# 4ESC_v3_1_1.net
KiCad netlist of a schematic drawn in EAGLE
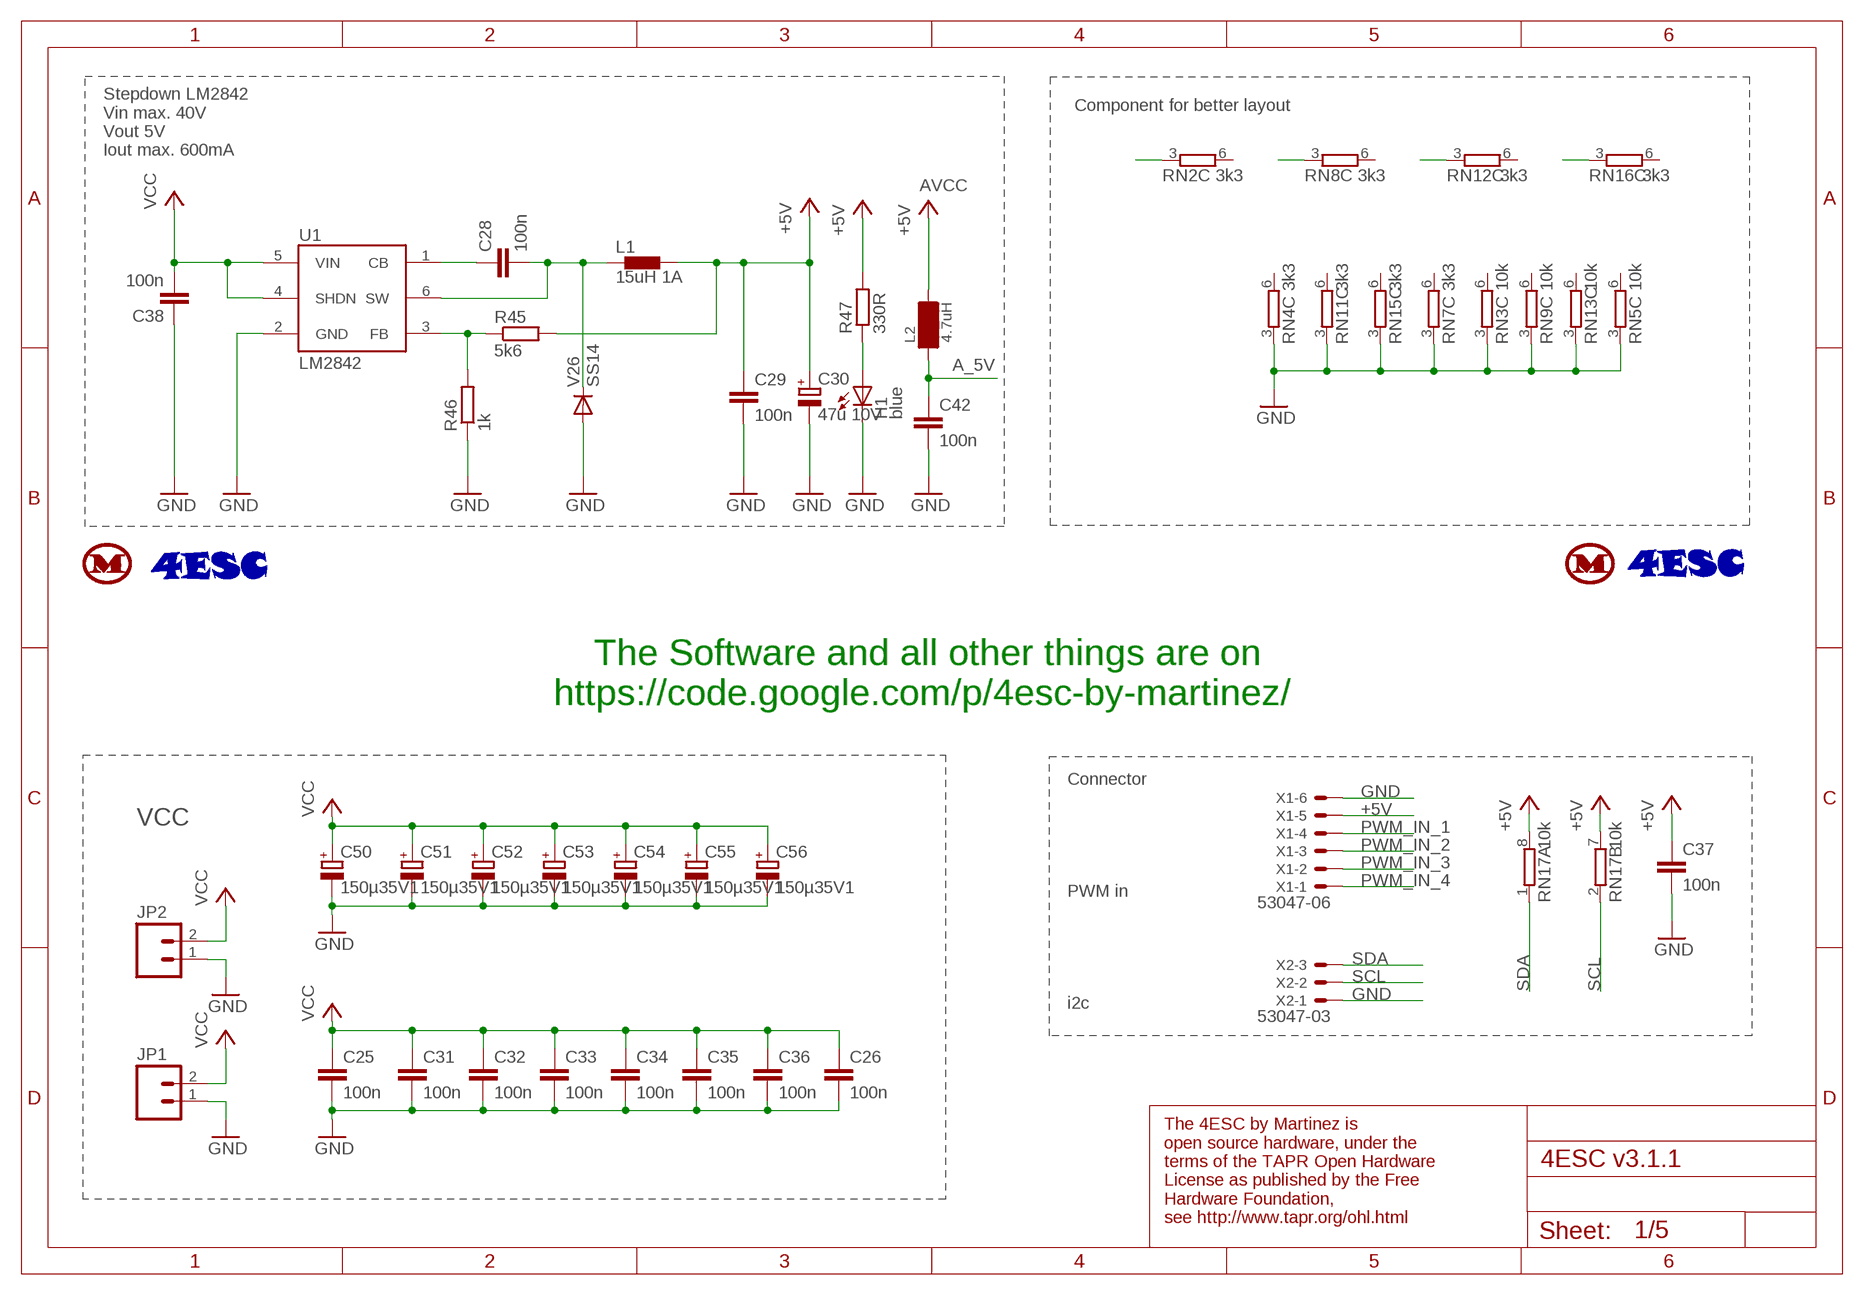
[diagram p0: schematic, sheet 1]
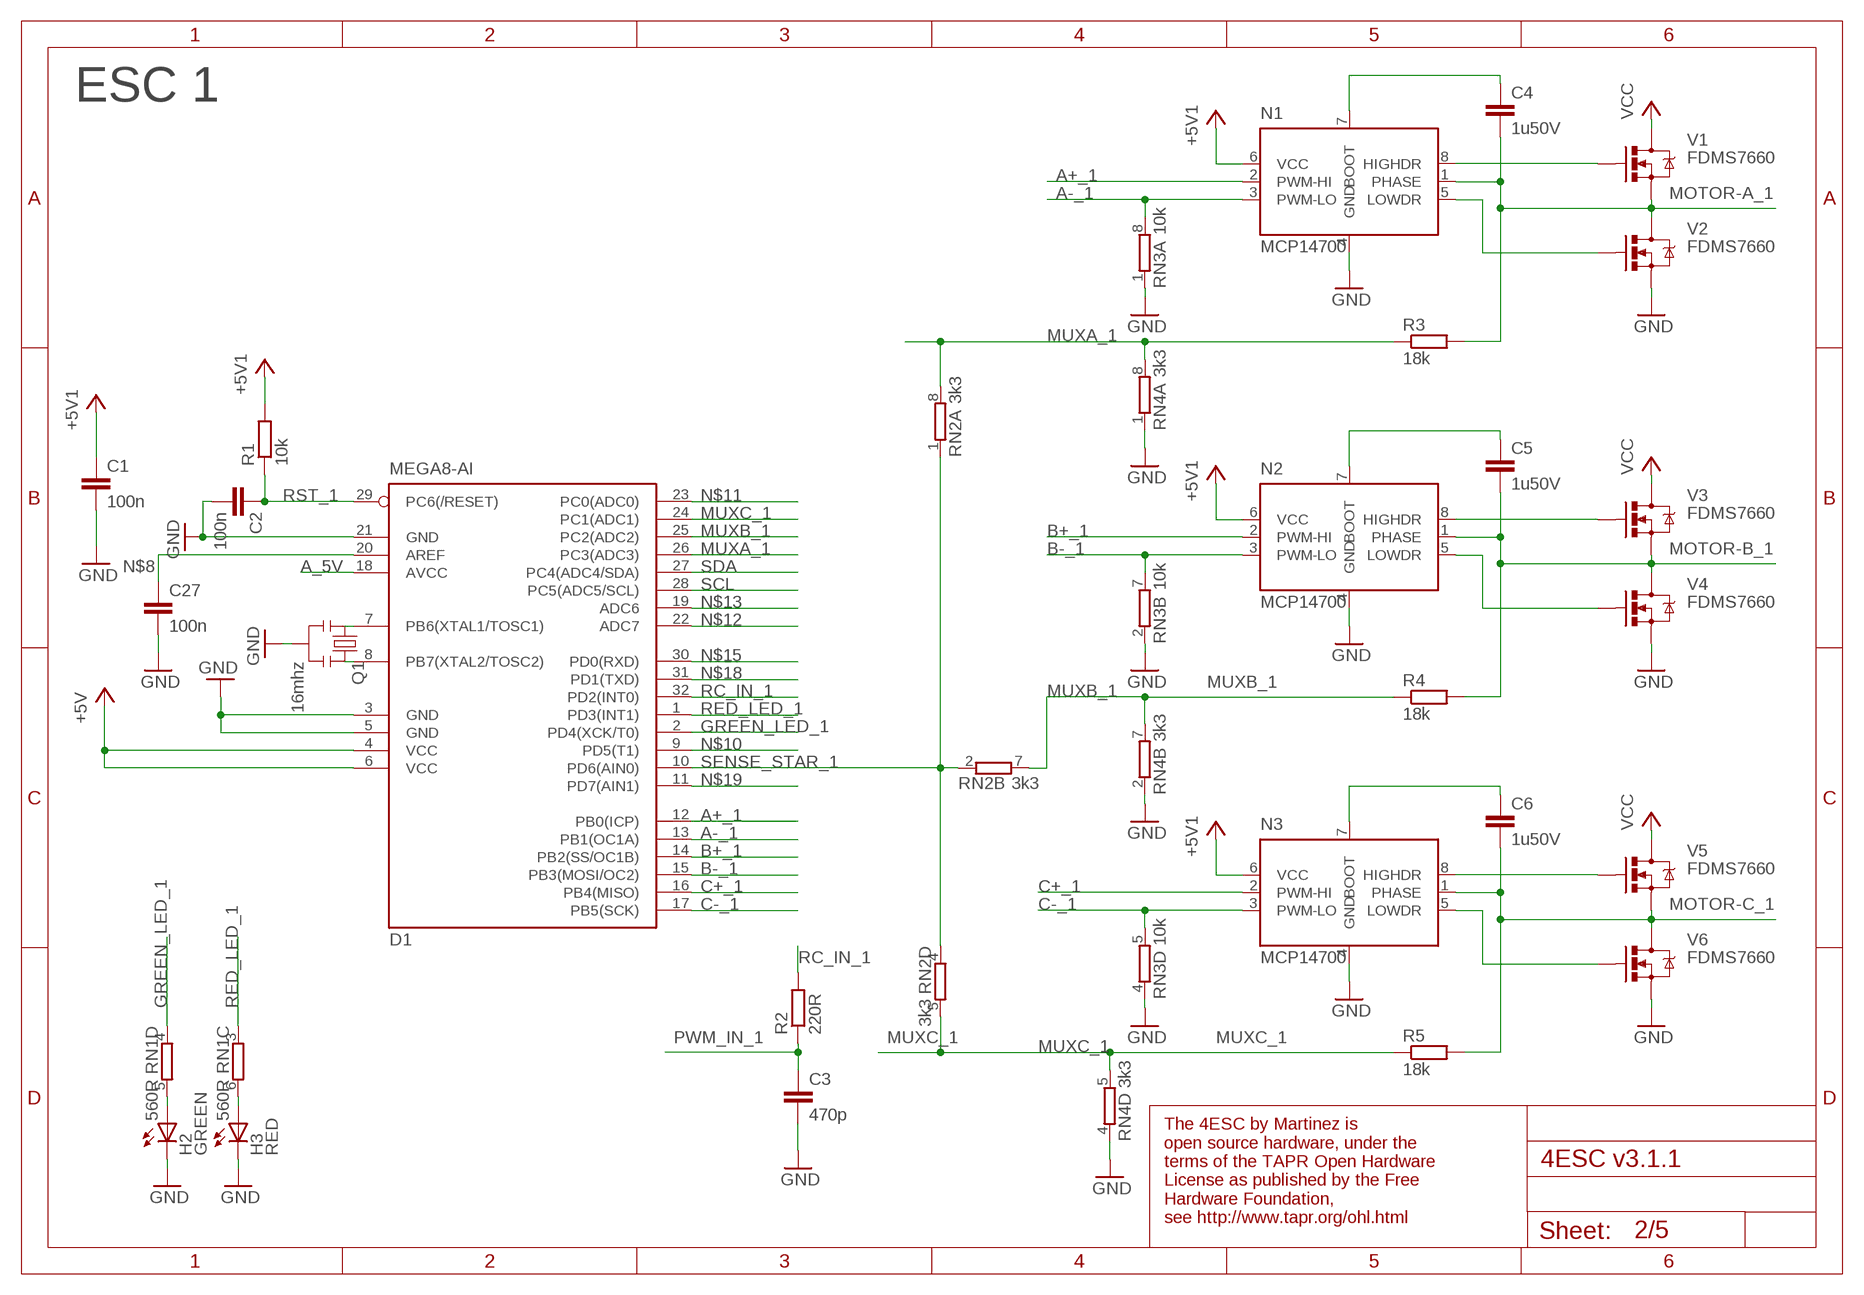
[diagram p1: schematic, sheet 2]
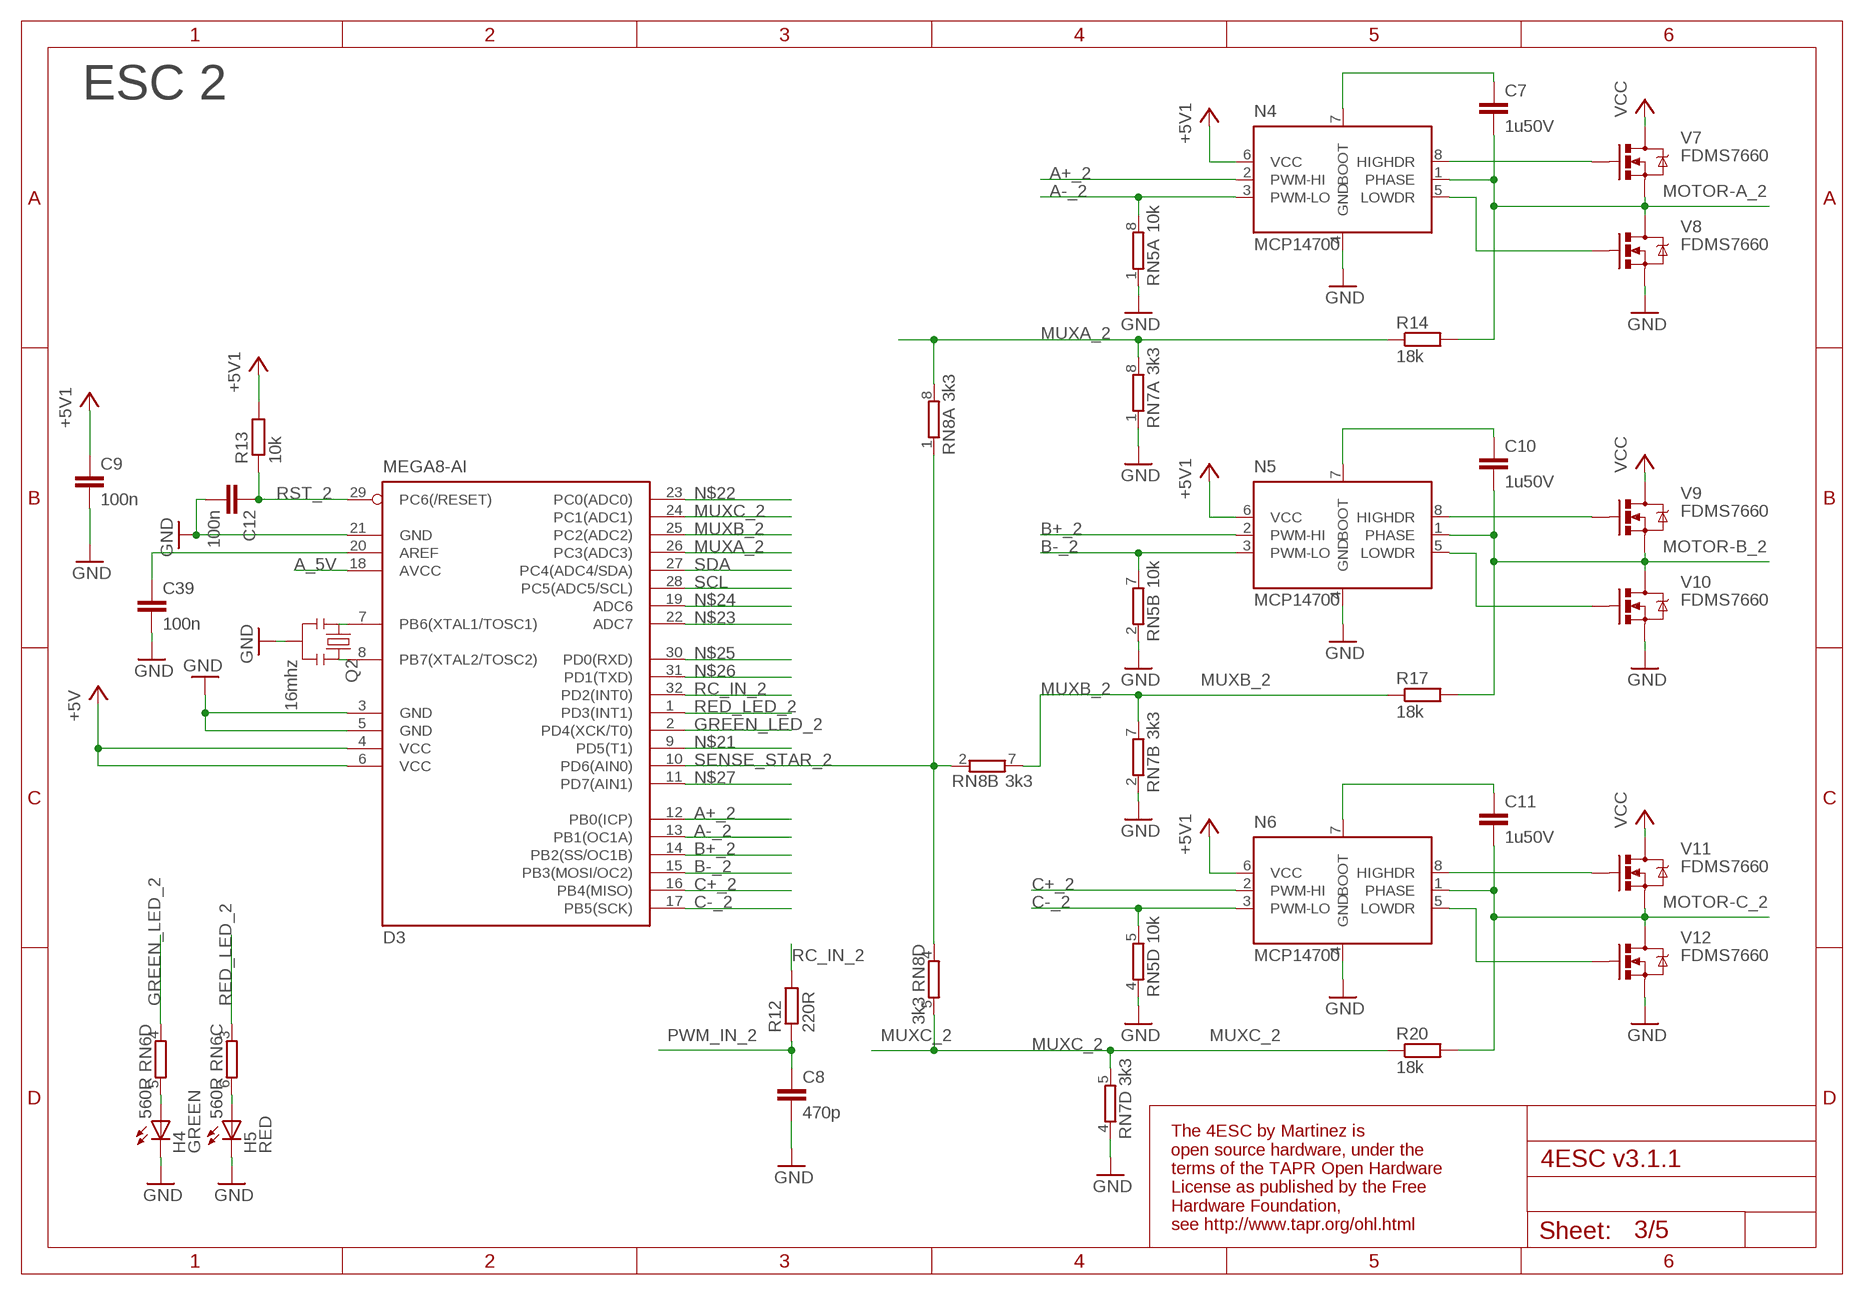
[diagram p2: schematic, sheet 3]
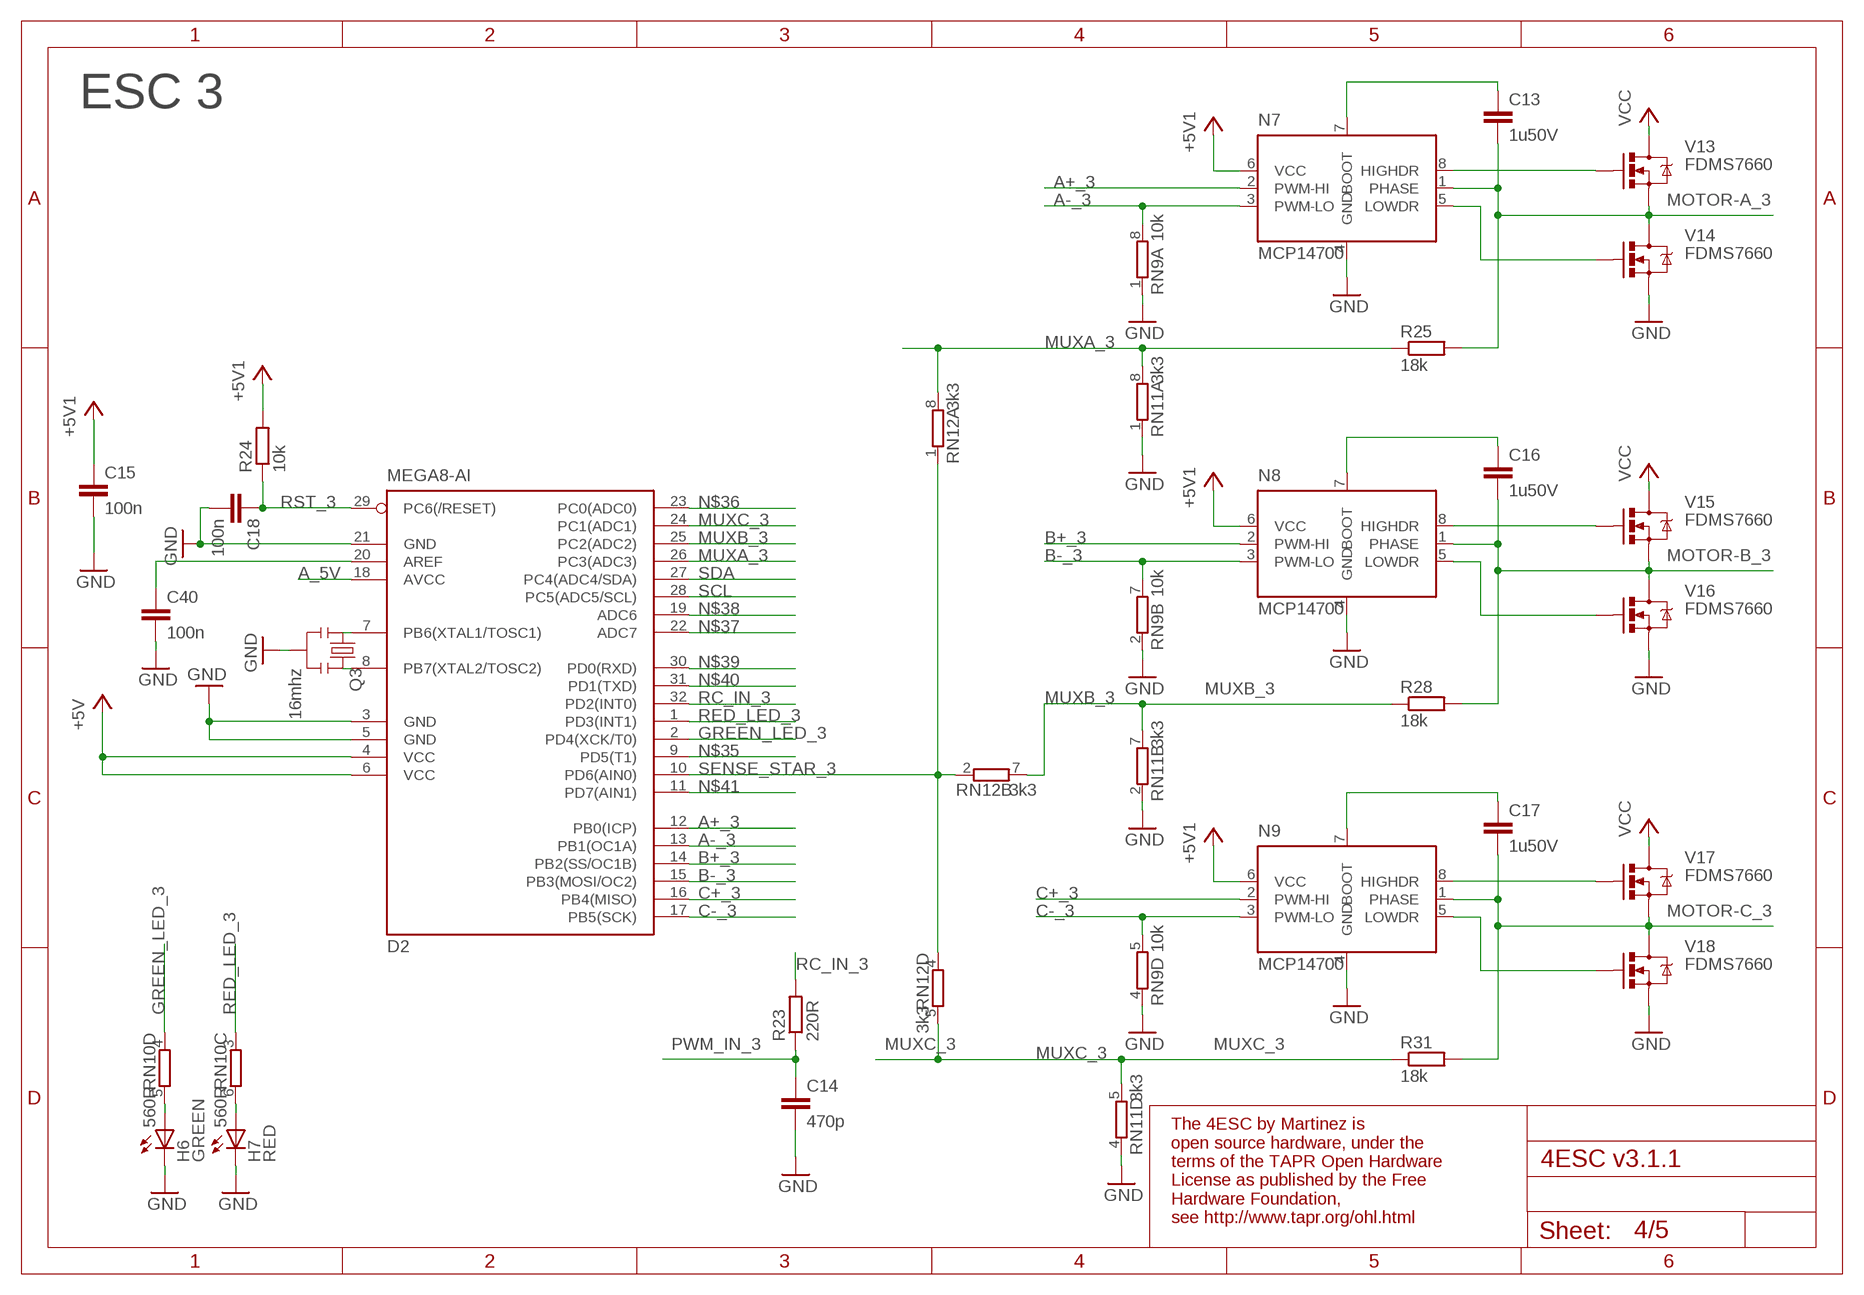
[diagram p3: schematic, sheet 4]
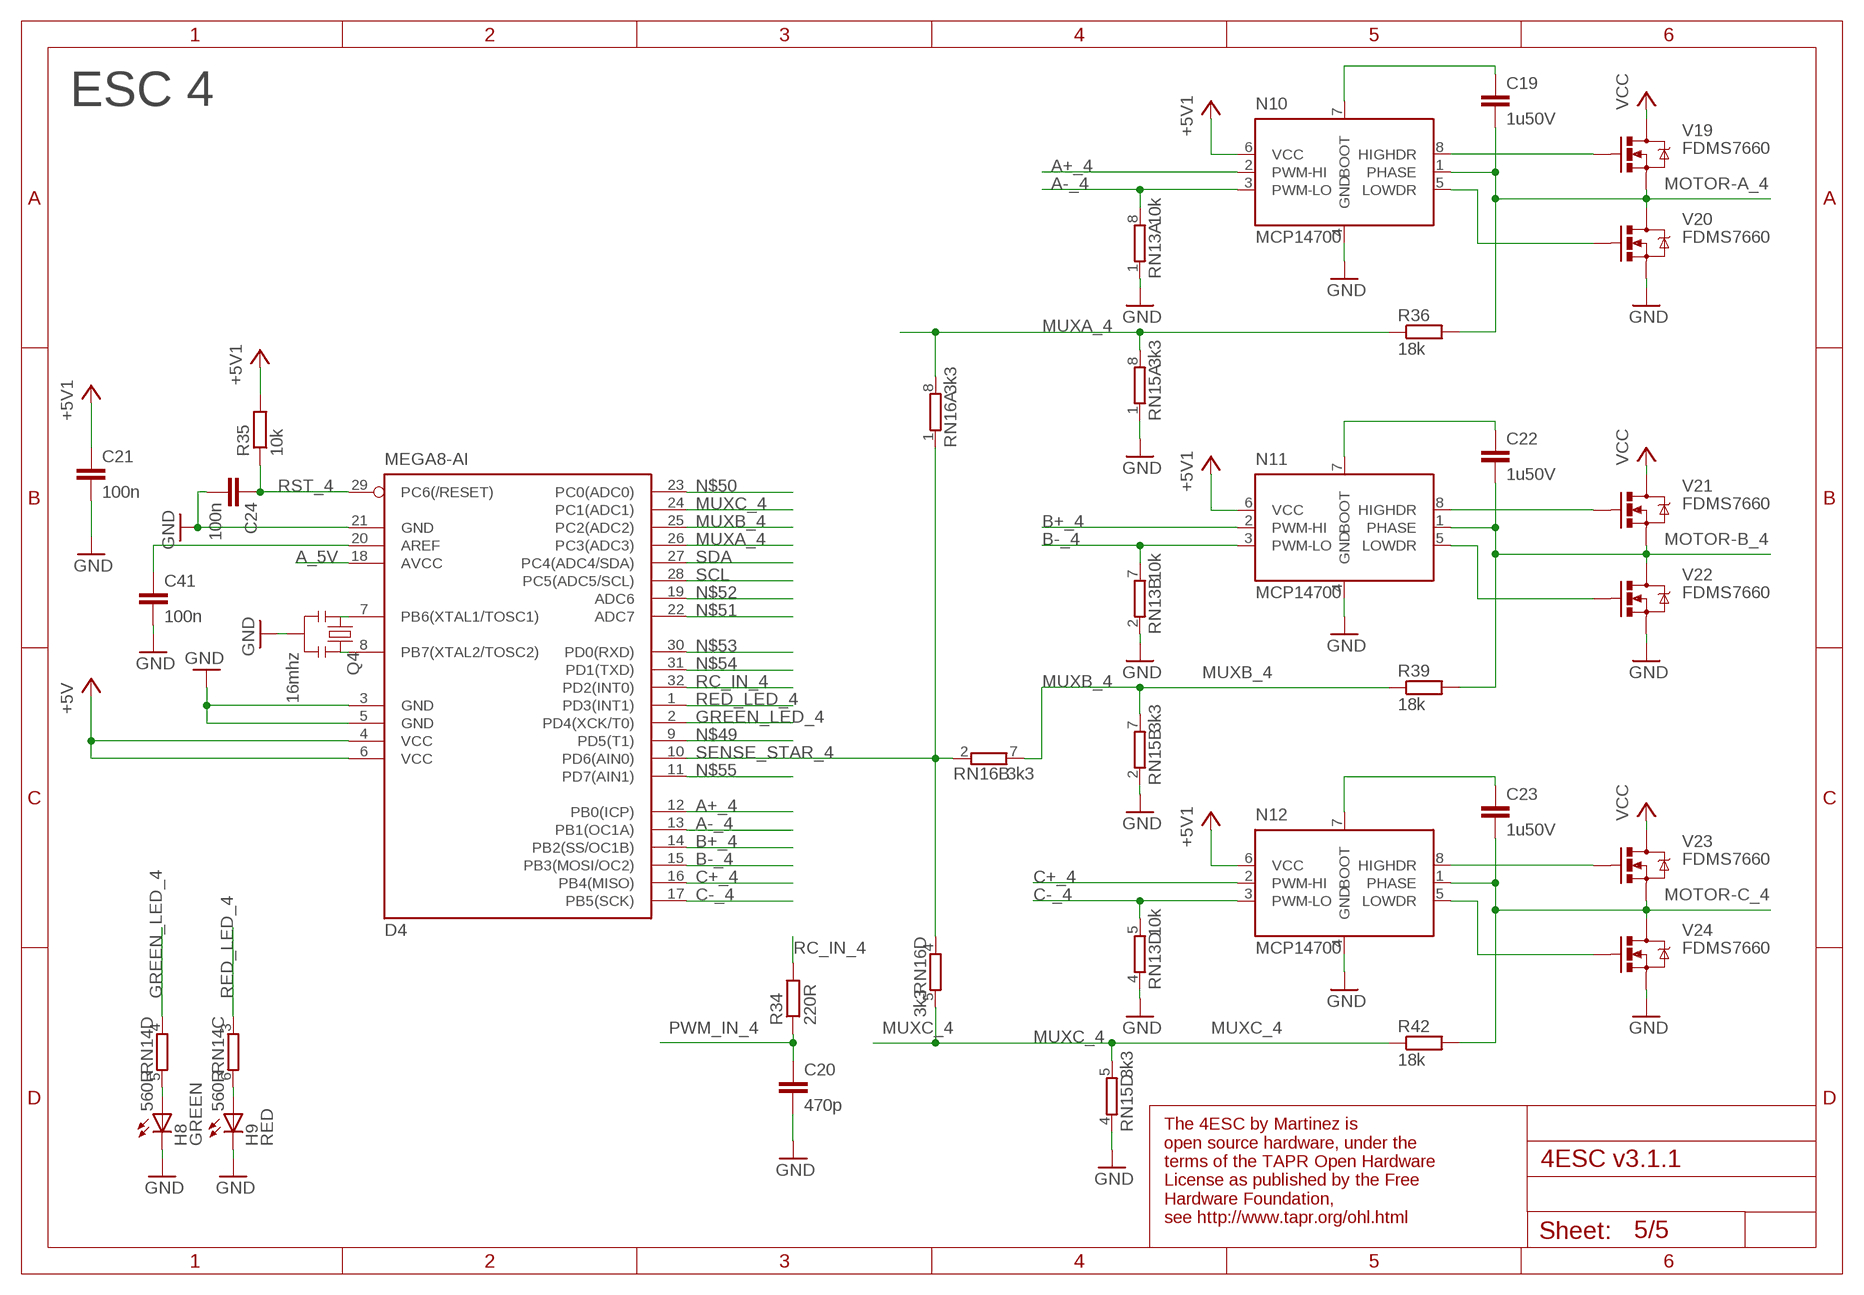
[diagram p4: schematic, sheet 5]

(export (version "E")
  (design (tool "Eeschema 10.0.6"))
  (components
    (comp (ref "C25")
      (value "100n")
      (footprint "eagle-import:C0603K")
      (libsource (lib "eagle-import") (part "C-EUC0603K"))
    )
    (comp (ref "C26")
      (value "100n")
      (footprint "eagle-import:C0603K")
      (libsource (lib "eagle-import") (part "C-EUC0603K"))
    )
    (comp (ref "C28")
      (value "100n")
      (footprint "eagle-import:C0603K")
      (libsource (lib "eagle-import") (part "C-EUC0603K"))
    )
    (comp (ref "C29")
      (value "100n")
      (footprint "eagle-import:C0603K")
      (libsource (lib "eagle-import") (part "C-EUC0603K"))
    )
    (comp (ref "C30")
      (value "47u 10V")
      (footprint "eagle-import:C_6032-28R")
      (libsource (lib "eagle-import") (part "CPOL-EUC/6032-28R"))
    )
    (comp (ref "C31")
      (value "100n")
      (footprint "eagle-import:C0603K")
      (libsource (lib "eagle-import") (part "C-EUC0603K"))
    )
    (comp (ref "C32")
      (value "100n")
      (footprint "eagle-import:C0603K")
      (libsource (lib "eagle-import") (part "C-EUC0603K"))
    )
    (comp (ref "C33")
      (value "100n")
      (footprint "eagle-import:C0603K")
      (libsource (lib "eagle-import") (part "C-EUC0603K"))
    )
    (comp (ref "C34")
      (value "100n")
      (footprint "eagle-import:C0603K")
      (libsource (lib "eagle-import") (part "C-EUC0603K"))
    )
    (comp (ref "C35")
      (value "100n")
      (footprint "eagle-import:C0603K")
      (libsource (lib "eagle-import") (part "C-EUC0603K"))
    )
    (comp (ref "C36")
      (value "100n")
      (footprint "eagle-import:C0603K")
      (libsource (lib "eagle-import") (part "C-EUC0603K"))
    )
    (comp (ref "C37")
      (value "100n")
      (footprint "eagle-import:C0603K")
      (libsource (lib "eagle-import") (part "C-EUC0603K"))
    )
    (comp (ref "C38")
      (value "100n")
      (footprint "eagle-import:C1206")
      (libsource (lib "eagle-import") (part "C-EUC1206"))
    )
    (comp (ref "C42")
      (value "100n")
      (footprint "eagle-import:C0603K")
      (libsource (lib "eagle-import") (part "C-EUC0603K"))
    )
    (comp (ref "C50")
      (value "150µ35V1")
      (footprint "eagle-import:ELKO_MARTINEZ")
      (libsource (lib "eagle-import") (part "CPOL-EU"))
    )
    (comp (ref "C51")
      (value "150µ35V1")
      (footprint "eagle-import:ELKO_MARTINEZ")
      (libsource (lib "eagle-import") (part "CPOL-EU"))
    )
    (comp (ref "C52")
      (value "150µ35V1")
      (footprint "eagle-import:ELKO_MARTINEZ")
      (libsource (lib "eagle-import") (part "CPOL-EU"))
    )
    (comp (ref "C53")
      (value "150µ35V1")
      (footprint "eagle-import:ELKO_MARTINEZ")
      (libsource (lib "eagle-import") (part "CPOL-EU"))
    )
    (comp (ref "C54")
      (value "150µ35V1")
      (footprint "eagle-import:ELKO_MARTINEZ")
      (libsource (lib "eagle-import") (part "CPOL-EU"))
    )
    (comp (ref "C55")
      (value "150µ35V1")
      (footprint "eagle-import:ELKO_MARTINEZ")
      (libsource (lib "eagle-import") (part "CPOL-EU"))
    )
    (comp (ref "C56")
      (value "150µ35V1")
      (footprint "eagle-import:ELKO_MARTINEZ")
      (libsource (lib "eagle-import") (part "CPOL-EU"))
    )
    (comp (ref "H1")
      (value "blue")
      (footprint "eagle-import:CHIPLED_0603")
      (libsource (lib "eagle-import") (part "LEDCHIPLED_0603"))
    )
    (comp (ref "JP1")
      (value "M021X02_NO_SILK")
      (footprint "eagle-import:1X02_NO_SILK")
      (libsource (lib "eagle-import") (part "M021X02_NO_SILK"))
    )
    (comp (ref "JP2")
      (value "M021X02_NO_SILK")
      (footprint "eagle-import:1X02_NO_SILK")
      (libsource (lib "eagle-import") (part "M021X02_NO_SILK"))
    )
    (comp (ref "L1")
      (value "15uH 1A")
      (footprint "eagle-import:CDRH4D28")
      (libsource (lib "eagle-import") (part "SUMIDA-CDRH4D28CDRH4D28"))
    )
    (comp (ref "L2")
      (value "4.7uH")
      (footprint "eagle-import:L0805")
      (libsource (lib "eagle-import") (part "L0805"))
    )
    (comp (ref "R45")
      (value "5k6")
      (footprint "eagle-import:R0603")
      (libsource (lib "eagle-import") (part "R-EU_R0603"))
    )
    (comp (ref "R46")
      (value "1k")
      (footprint "eagle-import:R0603")
      (libsource (lib "eagle-import") (part "R-EU_R0603"))
    )
    (comp (ref "R47")
      (value "330R")
      (footprint "eagle-import:R0603")
      (libsource (lib "eagle-import") (part "R-EU_R0603"))
    )
    (comp (ref "RN2")
      (value "3k3")
      (footprint "eagle-import:4X0402ARV341")
      (libsource (lib "eagle-import") (part "4R-N0402ARV341"))
    )
    (comp (ref "RN3")
      (value "10k")
      (footprint "eagle-import:4X0402ARV341")
      (libsource (lib "eagle-import") (part "4R-N0402ARV341"))
    )
    (comp (ref "RN4")
      (value "3k3")
      (footprint "eagle-import:4X0402ARV341")
      (libsource (lib "eagle-import") (part "4R-N0402ARV341"))
    )
    (comp (ref "RN5")
      (value "10k")
      (footprint "eagle-import:4X0402ARV341")
      (libsource (lib "eagle-import") (part "4R-N0402ARV341"))
    )
    (comp (ref "RN7")
      (value "3k3")
      (footprint "eagle-import:4X0402ARV341")
      (libsource (lib "eagle-import") (part "4R-N0402ARV341"))
    )
    (comp (ref "RN8")
      (value "3k3")
      (footprint "eagle-import:4X0402ARV341")
      (libsource (lib "eagle-import") (part "4R-N0402ARV341"))
    )
    (comp (ref "RN9")
      (value "10k")
      (footprint "eagle-import:4X0402ARV341")
      (libsource (lib "eagle-import") (part "4R-N0402ARV341"))
    )
    (comp (ref "RN11")
      (value "3k3")
      (footprint "eagle-import:4X0402ARV341")
      (libsource (lib "eagle-import") (part "4R-N0402ARV341"))
    )
    (comp (ref "RN12")
      (value "3k3")
      (footprint "eagle-import:4X0402ARV341")
      (libsource (lib "eagle-import") (part "4R-N0402ARV341"))
    )
    (comp (ref "RN13")
      (value "10k")
      (footprint "eagle-import:4X0402ARV341")
      (libsource (lib "eagle-import") (part "4R-N0402ARV341"))
    )
    (comp (ref "RN15")
      (value "3k3")
      (footprint "eagle-import:4X0402ARV341")
      (libsource (lib "eagle-import") (part "4R-N0402ARV341"))
    )
    (comp (ref "RN16")
      (value "3k3")
      (footprint "eagle-import:4X0402ARV341")
      (libsource (lib "eagle-import") (part "4R-N0402ARV341"))
    )
    (comp (ref "RN17")
      (value "10k")
      (footprint "eagle-import:4X0402ARV341")
      (libsource (lib "eagle-import") (part "4R-N0402ARV341"))
    )
    (comp (ref "U$1") (value "M") (footprint "eagle-import:M") (libsource (lib "eagle-import") (part "M")))
    (comp (ref "U$2") (value "M") (footprint "eagle-import:M") (libsource (lib "eagle-import") (part "M")))
    (comp (ref "U$3")
      (value "4ESC_05MM")
      (footprint "eagle-import:4ESC_05MM_HOCH")
      (libsource (lib "eagle-import") (part "4ESC_05MM"))
    )
    (comp (ref "U$4")
      (value "4ESC_05MM")
      (footprint "eagle-import:4ESC_05MM_HOCH")
      (libsource (lib "eagle-import") (part "4ESC_05MM"))
    )
    (comp (ref "U1")
      (value "LM2842")
      (footprint "eagle-import:SOT23-6")
      (libsource (lib "eagle-import") (part "LM2842"))
    )
    (comp (ref "V26")
      (value "SS14")
      (footprint "eagle-import:DO214AC")
      (libsource (lib "eagle-import") (part "DIODE-DO214AC"))
    )
    (comp (ref "X1")
      (value "53047-06")
      (footprint "eagle-import:53047-06")
      (fields (field (name "MPN") "53047-0610-C"))
      (libsource (lib "eagle-import") (part "53?-06047"))
    )
    (comp (ref "X2")
      (value "53047-03")
      (footprint "eagle-import:53047-03")
      (fields (field (name "MPN") "530470310"))
      (libsource (lib "eagle-import") (part "53?-03047"))
    )
    (comp (ref "C1")
      (value "100n")
      (footprint "eagle-import:C0603K")
      (libsource (lib "eagle-import") (part "resistor_C-EUC0603K"))
    )
    (comp (ref "C2")
      (value "100n")
      (footprint "eagle-import:C0603K")
      (libsource (lib "eagle-import") (part "resistor_C-EUC0603K"))
    )
    (comp (ref "C3")
      (value "470p")
      (footprint "eagle-import:C0603K")
      (libsource (lib "eagle-import") (part "C-EUC0603K"))
    )
    (comp (ref "C4")
      (value "1u50V")
      (footprint "eagle-import:C0805K")
      (libsource (lib "eagle-import") (part "C-EUC0805K"))
    )
    (comp (ref "C5")
      (value "1u50V")
      (footprint "eagle-import:C0805K")
      (libsource (lib "eagle-import") (part "C-EUC0805K"))
    )
    (comp (ref "C6")
      (value "1u50V")
      (footprint "eagle-import:C0805K")
      (libsource (lib "eagle-import") (part "C-EUC0805K"))
    )
    (comp (ref "C27")
      (value "100n")
      (footprint "eagle-import:C0603K")
      (libsource (lib "eagle-import") (part "resistor_C-EUC0603K"))
    )
    (comp (ref "D1")
      (value "MEGA8-AI")
      (footprint "eagle-import:TQFP32-08")
      (fields (field (name "MPN") "ATMEGA8-16AU"))
      (libsource (lib "eagle-import") (part "MEGA8-AI"))
    )
    (comp (ref "H2")
      (value "GREEN")
      (footprint "eagle-import:CHIPLED_0603")
      (libsource (lib "eagle-import") (part "LEDCHIPLED_0603"))
    )
    (comp (ref "H3")
      (value "RED")
      (footprint "eagle-import:CHIPLED_0603")
      (libsource (lib "eagle-import") (part "LEDCHIPLED_0603"))
    )
    (comp (ref "N1")
      (value "MCP14700")
      (footprint "eagle-import:DFN3X3P8")
      (libsource (lib "eagle-import") (part "MCP14700"))
    )
    (comp (ref "N2")
      (value "MCP14700")
      (footprint "eagle-import:DFN3X3P8")
      (libsource (lib "eagle-import") (part "MCP14700"))
    )
    (comp (ref "N3")
      (value "MCP14700")
      (footprint "eagle-import:DFN3X3P8")
      (libsource (lib "eagle-import") (part "MCP14700"))
    )
    (comp (ref "Q1")
      (value "16mhz")
      (footprint "eagle-import:RESONATOR-SMD")
      (libsource (lib "eagle-import") (part "RESONATORSMD"))
    )
    (comp (ref "R1")
      (value "10k")
      (footprint "eagle-import:R0603")
      (libsource (lib "eagle-import") (part "resistor_R-EU_R0603"))
    )
    (comp (ref "R2")
      (value "220R")
      (footprint "eagle-import:R0603")
      (libsource (lib "eagle-import") (part "resistor_R-EU_R0603"))
    )
    (comp (ref "R3")
      (value "18k")
      (footprint "eagle-import:R0603")
      (libsource (lib "eagle-import") (part "resistor_R-EU_R0603"))
    )
    (comp (ref "R4")
      (value "18k")
      (footprint "eagle-import:R0603")
      (libsource (lib "eagle-import") (part "resistor_R-EU_R0603"))
    )
    (comp (ref "R5")
      (value "18k")
      (footprint "eagle-import:R0603")
      (libsource (lib "eagle-import") (part "resistor_R-EU_R0603"))
    )
    (comp (ref "RN1")
      (value "560R")
      (footprint "eagle-import:4X0402ARV341")
      (libsource (lib "eagle-import") (part "4R-N0402ARV341"))
    )
    (comp (ref "V1")
      (value "FDMS7660")
      (footprint "eagle-import:POWER56")
      (libsource (lib "eagle-import") (part "FDMS7660"))
    )
    (comp (ref "V2")
      (value "FDMS7660")
      (footprint "eagle-import:POWER56")
      (libsource (lib "eagle-import") (part "FDMS7660"))
    )
    (comp (ref "V3")
      (value "FDMS7660")
      (footprint "eagle-import:POWER56")
      (libsource (lib "eagle-import") (part "FDMS7660"))
    )
    (comp (ref "V4")
      (value "FDMS7660")
      (footprint "eagle-import:POWER56")
      (libsource (lib "eagle-import") (part "FDMS7660"))
    )
    (comp (ref "V5")
      (value "FDMS7660")
      (footprint "eagle-import:POWER56")
      (libsource (lib "eagle-import") (part "FDMS7660"))
    )
    (comp (ref "V6")
      (value "FDMS7660")
      (footprint "eagle-import:POWER56")
      (libsource (lib "eagle-import") (part "FDMS7660"))
    )
    (comp (ref "C7")
      (value "1u50V")
      (footprint "eagle-import:C0805K")
      (libsource (lib "eagle-import") (part "C-EUC0805K"))
    )
    (comp (ref "C8")
      (value "470p")
      (footprint "eagle-import:C0603K")
      (libsource (lib "eagle-import") (part "C-EUC0603K"))
    )
    (comp (ref "C9")
      (value "100n")
      (footprint "eagle-import:C0603K")
      (libsource (lib "eagle-import") (part "resistor_C-EUC0603K"))
    )
    (comp (ref "C10")
      (value "1u50V")
      (footprint "eagle-import:C0805K")
      (libsource (lib "eagle-import") (part "C-EUC0805K"))
    )
    (comp (ref "C11")
      (value "1u50V")
      (footprint "eagle-import:C0805K")
      (libsource (lib "eagle-import") (part "C-EUC0805K"))
    )
    (comp (ref "C12")
      (value "100n")
      (footprint "eagle-import:C0603K")
      (libsource (lib "eagle-import") (part "resistor_C-EUC0603K"))
    )
    (comp (ref "C39")
      (value "100n")
      (footprint "eagle-import:C0603K")
      (libsource (lib "eagle-import") (part "resistor_C-EUC0603K"))
    )
    (comp (ref "D3")
      (value "MEGA8-AI")
      (footprint "eagle-import:TQFP32-08")
      (fields (field (name "MPN") "ATMEGA8-16AU"))
      (libsource (lib "eagle-import") (part "MEGA8-AI"))
    )
    (comp (ref "H4")
      (value "GREEN")
      (footprint "eagle-import:CHIPLED_0603")
      (libsource (lib "eagle-import") (part "LEDCHIPLED_0603"))
    )
    (comp (ref "H5")
      (value "RED")
      (footprint "eagle-import:CHIPLED_0603")
      (libsource (lib "eagle-import") (part "LEDCHIPLED_0603"))
    )
    (comp (ref "N4")
      (value "MCP14700")
      (footprint "eagle-import:DFN3X3P8")
      (libsource (lib "eagle-import") (part "MCP14700"))
    )
    (comp (ref "N5")
      (value "MCP14700")
      (footprint "eagle-import:DFN3X3P8")
      (libsource (lib "eagle-import") (part "MCP14700"))
    )
    (comp (ref "N6")
      (value "MCP14700")
      (footprint "eagle-import:DFN3X3P8")
      (libsource (lib "eagle-import") (part "MCP14700"))
    )
    (comp (ref "Q2")
      (value "16mhz")
      (footprint "eagle-import:RESONATOR-SMD")
      (libsource (lib "eagle-import") (part "RESONATORSMD"))
    )
    (comp (ref "R12")
      (value "220R")
      (footprint "eagle-import:R0603")
      (libsource (lib "eagle-import") (part "resistor_R-EU_R0603"))
    )
    (comp (ref "R13")
      (value "10k")
      (footprint "eagle-import:R0603")
      (libsource (lib "eagle-import") (part "resistor_R-EU_R0603"))
    )
    (comp (ref "R14")
      (value "18k")
      (footprint "eagle-import:R0603")
      (libsource (lib "eagle-import") (part "resistor_R-EU_R0603"))
    )
    (comp (ref "R17")
      (value "18k")
      (footprint "eagle-import:R0603")
      (libsource (lib "eagle-import") (part "resistor_R-EU_R0603"))
    )
    (comp (ref "R20")
      (value "18k")
      (footprint "eagle-import:R0603")
      (libsource (lib "eagle-import") (part "resistor_R-EU_R0603"))
    )
    (comp (ref "RN6")
      (value "560R")
      (footprint "eagle-import:4X0402ARV341")
      (libsource (lib "eagle-import") (part "4R-N0402ARV341"))
    )
    (comp (ref "V7")
      (value "FDMS7660")
      (footprint "eagle-import:POWER56")
      (libsource (lib "eagle-import") (part "FDMS7660"))
    )
    (comp (ref "V8")
      (value "FDMS7660")
      (footprint "eagle-import:POWER56")
      (libsource (lib "eagle-import") (part "FDMS7660"))
    )
    (comp (ref "V9")
      (value "FDMS7660")
      (footprint "eagle-import:POWER56")
      (libsource (lib "eagle-import") (part "FDMS7660"))
    )
    (comp (ref "V10")
      (value "FDMS7660")
      (footprint "eagle-import:POWER56")
      (libsource (lib "eagle-import") (part "FDMS7660"))
    )
    (comp (ref "V11")
      (value "FDMS7660")
      (footprint "eagle-import:POWER56")
      (libsource (lib "eagle-import") (part "FDMS7660"))
    )
    (comp (ref "V12")
      (value "FDMS7660")
      (footprint "eagle-import:POWER56")
      (libsource (lib "eagle-import") (part "FDMS7660"))
    )
    (comp (ref "C19")
      (value "1u50V")
      (footprint "eagle-import:C0805K")
      (libsource (lib "eagle-import") (part "C-EUC0805K"))
    )
    (comp (ref "C20")
      (value "470p")
      (footprint "eagle-import:C0603K")
      (libsource (lib "eagle-import") (part "C-EUC0603K"))
    )
    (comp (ref "C21")
      (value "100n")
      (footprint "eagle-import:C0603K")
      (libsource (lib "eagle-import") (part "resistor_C-EUC0603K"))
    )
    (comp (ref "C22")
      (value "1u50V")
      (footprint "eagle-import:C0805K")
      (libsource (lib "eagle-import") (part "C-EUC0805K"))
    )
    (comp (ref "C23")
      (value "1u50V")
      (footprint "eagle-import:C0805K")
      (libsource (lib "eagle-import") (part "C-EUC0805K"))
    )
    (comp (ref "C24")
      (value "100n")
      (footprint "eagle-import:C0603K")
      (libsource (lib "eagle-import") (part "resistor_C-EUC0603K"))
    )
    (comp (ref "C41")
      (value "100n")
      (footprint "eagle-import:C0603K")
      (libsource (lib "eagle-import") (part "resistor_C-EUC0603K"))
    )
    (comp (ref "D4")
      (value "MEGA8-AI")
      (footprint "eagle-import:TQFP32-08")
      (fields (field (name "MPN") "ATMEGA8-16AU"))
      (libsource (lib "eagle-import") (part "MEGA8-AI"))
    )
    (comp (ref "H8")
      (value "GREEN")
      (footprint "eagle-import:CHIPLED_0603")
      (libsource (lib "eagle-import") (part "LEDCHIPLED_0603"))
    )
    (comp (ref "H9")
      (value "RED")
      (footprint "eagle-import:CHIPLED_0603")
      (libsource (lib "eagle-import") (part "LEDCHIPLED_0603"))
    )
    (comp (ref "N10")
      (value "MCP14700")
      (footprint "eagle-import:DFN3X3P8")
      (libsource (lib "eagle-import") (part "MCP14700"))
    )
    (comp (ref "N11")
      (value "MCP14700")
      (footprint "eagle-import:DFN3X3P8")
      (libsource (lib "eagle-import") (part "MCP14700"))
    )
    (comp (ref "N12")
      (value "MCP14700")
      (footprint "eagle-import:DFN3X3P8")
      (libsource (lib "eagle-import") (part "MCP14700"))
    )
    (comp (ref "Q4")
      (value "16mhz")
      (footprint "eagle-import:RESONATOR-SMD")
      (libsource (lib "eagle-import") (part "RESONATORSMD"))
    )
    (comp (ref "R34")
      (value "220R")
      (footprint "eagle-import:R0603")
      (libsource (lib "eagle-import") (part "resistor_R-EU_R0603"))
    )
    (comp (ref "R35")
      (value "10k")
      (footprint "eagle-import:R0603")
      (libsource (lib "eagle-import") (part "resistor_R-EU_R0603"))
    )
    (comp (ref "R36")
      (value "18k")
      (footprint "eagle-import:R0603")
      (libsource (lib "eagle-import") (part "resistor_R-EU_R0603"))
    )
    (comp (ref "R39")
      (value "18k")
      (footprint "eagle-import:R0603")
      (libsource (lib "eagle-import") (part "resistor_R-EU_R0603"))
    )
    (comp (ref "R42")
      (value "18k")
      (footprint "eagle-import:R0603")
      (libsource (lib "eagle-import") (part "resistor_R-EU_R0603"))
    )
    (comp (ref "RN14")
      (value "560R")
      (footprint "eagle-import:4X0402ARV341")
      (libsource (lib "eagle-import") (part "4R-N0402ARV341"))
    )
    (comp (ref "V19")
      (value "FDMS7660")
      (footprint "eagle-import:POWER56")
      (libsource (lib "eagle-import") (part "FDMS7660"))
    )
    (comp (ref "V20")
      (value "FDMS7660")
      (footprint "eagle-import:POWER56")
      (libsource (lib "eagle-import") (part "FDMS7660"))
    )
    (comp (ref "V21")
      (value "FDMS7660")
      (footprint "eagle-import:POWER56")
      (libsource (lib "eagle-import") (part "FDMS7660"))
    )
    (comp (ref "V22")
      (value "FDMS7660")
      (footprint "eagle-import:POWER56")
      (libsource (lib "eagle-import") (part "FDMS7660"))
    )
    (comp (ref "V23")
      (value "FDMS7660")
      (footprint "eagle-import:POWER56")
      (libsource (lib "eagle-import") (part "FDMS7660"))
    )
    (comp (ref "V24")
      (value "FDMS7660")
      (footprint "eagle-import:POWER56")
      (libsource (lib "eagle-import") (part "FDMS7660"))
    )
    (comp (ref "C13")
      (value "1u50V")
      (footprint "eagle-import:C0805K")
      (libsource (lib "eagle-import") (part "C-EUC0805K"))
    )
    (comp (ref "C14")
      (value "470p")
      (footprint "eagle-import:C0603K")
      (libsource (lib "eagle-import") (part "C-EUC0603K"))
    )
    (comp (ref "C15")
      (value "100n")
      (footprint "eagle-import:C0603K")
      (libsource (lib "eagle-import") (part "resistor_C-EUC0603K"))
    )
    (comp (ref "C16")
      (value "1u50V")
      (footprint "eagle-import:C0805K")
      (libsource (lib "eagle-import") (part "C-EUC0805K"))
    )
    (comp (ref "C17")
      (value "1u50V")
      (footprint "eagle-import:C0805K")
      (libsource (lib "eagle-import") (part "C-EUC0805K"))
    )
    (comp (ref "C18")
      (value "100n")
      (footprint "eagle-import:C0603K")
      (libsource (lib "eagle-import") (part "resistor_C-EUC0603K"))
    )
    (comp (ref "C40")
      (value "100n")
      (footprint "eagle-import:C0603K")
      (libsource (lib "eagle-import") (part "resistor_C-EUC0603K"))
    )
    (comp (ref "D2")
      (value "MEGA8-AI")
      (footprint "eagle-import:TQFP32-08")
      (fields (field (name "MPN") "ATMEGA8-16AU"))
      (libsource (lib "eagle-import") (part "MEGA8-AI"))
    )
    (comp (ref "H6")
      (value "GREEN")
      (footprint "eagle-import:CHIPLED_0603")
      (libsource (lib "eagle-import") (part "LEDCHIPLED_0603"))
    )
    (comp (ref "H7")
      (value "RED")
      (footprint "eagle-import:CHIPLED_0603")
      (libsource (lib "eagle-import") (part "LEDCHIPLED_0603"))
    )
    (comp (ref "N7")
      (value "MCP14700")
      (footprint "eagle-import:DFN3X3P8")
      (libsource (lib "eagle-import") (part "MCP14700"))
    )
    (comp (ref "N8")
      (value "MCP14700")
      (footprint "eagle-import:DFN3X3P8")
      (libsource (lib "eagle-import") (part "MCP14700"))
    )
    (comp (ref "N9")
      (value "MCP14700")
      (footprint "eagle-import:DFN3X3P8")
      (libsource (lib "eagle-import") (part "MCP14700"))
    )
    (comp (ref "Q3")
      (value "16mhz")
      (footprint "eagle-import:RESONATOR-SMD")
      (libsource (lib "eagle-import") (part "RESONATORSMD"))
    )
    (comp (ref "R23")
      (value "220R")
      (footprint "eagle-import:R0603")
      (libsource (lib "eagle-import") (part "resistor_R-EU_R0603"))
    )
    (comp (ref "R24")
      (value "10k")
      (footprint "eagle-import:R0603")
      (libsource (lib "eagle-import") (part "resistor_R-EU_R0603"))
    )
    (comp (ref "R25")
      (value "18k")
      (footprint "eagle-import:R0603")
      (libsource (lib "eagle-import") (part "resistor_R-EU_R0603"))
    )
    (comp (ref "R28")
      (value "18k")
      (footprint "eagle-import:R0603")
      (libsource (lib "eagle-import") (part "resistor_R-EU_R0603"))
    )
    (comp (ref "R31")
      (value "18k")
      (footprint "eagle-import:R0603")
      (libsource (lib "eagle-import") (part "resistor_R-EU_R0603"))
    )
    (comp (ref "RN10")
      (value "560R")
      (footprint "eagle-import:4X0402ARV341")
      (libsource (lib "eagle-import") (part "4R-N0402ARV341"))
    )
    (comp (ref "V13")
      (value "FDMS7660")
      (footprint "eagle-import:POWER56")
      (libsource (lib "eagle-import") (part "FDMS7660"))
    )
    (comp (ref "V14")
      (value "FDMS7660")
      (footprint "eagle-import:POWER56")
      (libsource (lib "eagle-import") (part "FDMS7660"))
    )
    (comp (ref "V15")
      (value "FDMS7660")
      (footprint "eagle-import:POWER56")
      (libsource (lib "eagle-import") (part "FDMS7660"))
    )
    (comp (ref "V16")
      (value "FDMS7660")
      (footprint "eagle-import:POWER56")
      (libsource (lib "eagle-import") (part "FDMS7660"))
    )
    (comp (ref "V17")
      (value "FDMS7660")
      (footprint "eagle-import:POWER56")
      (libsource (lib "eagle-import") (part "FDMS7660"))
    )
    (comp (ref "V18")
      (value "FDMS7660")
      (footprint "eagle-import:POWER56")
      (libsource (lib "eagle-import") (part "FDMS7660"))
    )
  )
  (nets
    (net (code "1") (name "+5V") (class "Default")
      (node (ref "C1") (pin "1") (pinfunction "1_1") (pintype "passive"))
      (node (ref "C15") (pin "1") (pinfunction "1_1") (pintype "passive"))
      (node (ref "C21") (pin "1") (pinfunction "1_1") (pintype "passive"))
      (node (ref "C29") (pin "1") (pinfunction "1_1") (pintype "passive"))
      (node (ref "C30") (pin "+") (pinfunction "+_+") (pintype "passive"))
      (node (ref "C37") (pin "1") (pinfunction "1_1") (pintype "passive"))
      (node (ref "C9") (pin "1") (pinfunction "1_1") (pintype "passive"))
      (node (ref "D1") (pin "4") (pinfunction "VCC_4") (pintype "power_in"))
      (node (ref "D1") (pin "6") (pinfunction "VCC_6") (pintype "power_in"))
      (node (ref "D2") (pin "4") (pinfunction "VCC_4") (pintype "power_in"))
      (node (ref "D2") (pin "6") (pinfunction "VCC_6") (pintype "power_in"))
      (node (ref "D3") (pin "4") (pinfunction "VCC_4") (pintype "power_in"))
      (node (ref "D3") (pin "6") (pinfunction "VCC_6") (pintype "power_in"))
      (node (ref "D4") (pin "4") (pinfunction "VCC_4") (pintype "power_in"))
      (node (ref "D4") (pin "6") (pinfunction "VCC_6") (pintype "power_in"))
      (node (ref "L1") (pin "P$2") (pinfunction "2_P$2") (pintype "passive"))
      (node (ref "L2") (pin "2") (pinfunction "2_2") (pintype "passive"))
      (node (ref "N1") (pin "6") (pinfunction "VCC_6") (pintype "power_in"))
      (node (ref "N10") (pin "6") (pinfunction "VCC_6") (pintype "power_in"))
      (node (ref "N11") (pin "6") (pinfunction "VCC_6") (pintype "power_in"))
      (node (ref "N12") (pin "6") (pinfunction "VCC_6") (pintype "power_in"))
      (node (ref "N2") (pin "6") (pinfunction "VCC_6") (pintype "power_in"))
      (node (ref "N3") (pin "6") (pinfunction "VCC_6") (pintype "power_in"))
      (node (ref "N4") (pin "6") (pinfunction "VCC_6") (pintype "power_in"))
      (node (ref "N5") (pin "6") (pinfunction "VCC_6") (pintype "power_in"))
      (node (ref "N6") (pin "6") (pinfunction "VCC_6") (pintype "power_in"))
      (node (ref "N7") (pin "6") (pinfunction "VCC_6") (pintype "power_in"))
      (node (ref "N8") (pin "6") (pinfunction "VCC_6") (pintype "power_in"))
      (node (ref "N9") (pin "6") (pinfunction "VCC_6") (pintype "power_in"))
      (node (ref "R1") (pin "2") (pinfunction "2_2") (pintype "passive"))
      (node (ref "R13") (pin "2") (pinfunction "2_2") (pintype "passive"))
      (node (ref "R24") (pin "2") (pinfunction "2_2") (pintype "passive"))
      (node (ref "R35") (pin "2") (pinfunction "2_2") (pintype "passive"))
      (node (ref "R45") (pin "2") (pinfunction "2_2") (pintype "passive"))
      (node (ref "R47") (pin "2") (pinfunction "2_2") (pintype "passive"))
      (node (ref "RN17") (pin "7") (pinfunction "2_7") (pintype "passive"))
      (node (ref "RN17") (pin "8") (pinfunction "2_8") (pintype "passive"))
      (node (ref "X1") (pin "5") (pinfunction "S_5") (pintype "passive"))
    )
    (net (code "2") (name "A+_1") (class "Default")
      (node (ref "D1") (pin "12") (pinfunction "PB0(ICP)_12") (pintype "bidirectional"))
      (node (ref "N1") (pin "2") (pinfunction "PWM-HI_2") (pintype "input"))
    )
    (net (code "3") (name "A+_2") (class "Default")
      (node (ref "D3") (pin "12") (pinfunction "PB0(ICP)_12") (pintype "bidirectional"))
      (node (ref "N4") (pin "2") (pinfunction "PWM-HI_2") (pintype "input"))
    )
    (net (code "4") (name "A+_3") (class "Default")
      (node (ref "D2") (pin "12") (pinfunction "PB0(ICP)_12") (pintype "bidirectional"))
      (node (ref "N7") (pin "2") (pinfunction "PWM-HI_2") (pintype "input"))
    )
    (net (code "5") (name "A+_4") (class "Default")
      (node (ref "D4") (pin "12") (pinfunction "PB0(ICP)_12") (pintype "bidirectional"))
      (node (ref "N10") (pin "2") (pinfunction "PWM-HI_2") (pintype "input"))
    )
    (net (code "6") (name "A-_1") (class "Default")
      (node (ref "D1") (pin "13") (pinfunction "PB1(OC1A)_13") (pintype "bidirectional"))
      (node (ref "N1") (pin "3") (pinfunction "PWM-LO_3") (pintype "input"))
      (node (ref "RN3") (pin "8") (pinfunction "2_8") (pintype "passive"))
    )
    (net (code "7") (name "A-_2") (class "Default")
      (node (ref "D3") (pin "13") (pinfunction "PB1(OC1A)_13") (pintype "bidirectional"))
      (node (ref "N4") (pin "3") (pinfunction "PWM-LO_3") (pintype "input"))
      (node (ref "RN5") (pin "8") (pinfunction "2_8") (pintype "passive"))
    )
    (net (code "8") (name "A-_3") (class "Default")
      (node (ref "D2") (pin "13") (pinfunction "PB1(OC1A)_13") (pintype "bidirectional"))
      (node (ref "N7") (pin "3") (pinfunction "PWM-LO_3") (pintype "input"))
      (node (ref "RN9") (pin "8") (pinfunction "2_8") (pintype "passive"))
    )
    (net (code "9") (name "A-_4") (class "Default")
      (node (ref "D4") (pin "13") (pinfunction "PB1(OC1A)_13") (pintype "bidirectional"))
      (node (ref "N10") (pin "3") (pinfunction "PWM-LO_3") (pintype "input"))
      (node (ref "RN13") (pin "8") (pinfunction "2_8") (pintype "passive"))
    )
    (net (code "10") (name "A_5V") (class "Default")
      (node (ref "C42") (pin "1") (pinfunction "1_1") (pintype "passive"))
      (node (ref "D1") (pin "18") (pinfunction "AVCC_18") (pintype "power_in"))
      (node (ref "D2") (pin "18") (pinfunction "AVCC_18") (pintype "power_in"))
      (node (ref "D3") (pin "18") (pinfunction "AVCC_18") (pintype "power_in"))
      (node (ref "D4") (pin "18") (pinfunction "AVCC_18") (pintype "power_in"))
      (node (ref "L2") (pin "1") (pinfunction "1_1") (pintype "passive"))
    )
    (net (code "11") (name "B+_1") (class "Default")
      (node (ref "D1") (pin "14") (pinfunction "PB2(SS/OC1B)_14") (pintype "bidirectional"))
      (node (ref "N2") (pin "2") (pinfunction "PWM-HI_2") (pintype "input"))
    )
    (net (code "12") (name "B+_2") (class "Default")
      (node (ref "D3") (pin "14") (pinfunction "PB2(SS/OC1B)_14") (pintype "bidirectional"))
      (node (ref "N5") (pin "2") (pinfunction "PWM-HI_2") (pintype "input"))
    )
    (net (code "13") (name "B+_3") (class "Default")
      (node (ref "D2") (pin "14") (pinfunction "PB2(SS/OC1B)_14") (pintype "bidirectional"))
      (node (ref "N8") (pin "2") (pinfunction "PWM-HI_2") (pintype "input"))
    )
    (net (code "14") (name "B+_4") (class "Default")
      (node (ref "D4") (pin "14") (pinfunction "PB2(SS/OC1B)_14") (pintype "bidirectional"))
      (node (ref "N11") (pin "2") (pinfunction "PWM-HI_2") (pintype "input"))
    )
    (net (code "15") (name "B-_1") (class "Default")
      (node (ref "D1") (pin "15") (pinfunction "PB3(MOSI/OC2)_15") (pintype "bidirectional"))
      (node (ref "N2") (pin "3") (pinfunction "PWM-LO_3") (pintype "input"))
      (node (ref "RN3") (pin "7") (pinfunction "2_7") (pintype "passive"))
    )
    (net (code "16") (name "B-_2") (class "Default")
      (node (ref "D3") (pin "15") (pinfunction "PB3(MOSI/OC2)_15") (pintype "bidirectional"))
      (node (ref "N5") (pin "3") (pinfunction "PWM-LO_3") (pintype "input"))
      (node (ref "RN5") (pin "7") (pinfunction "2_7") (pintype "passive"))
    )
    (net (code "17") (name "B-_3") (class "Default")
      (node (ref "D2") (pin "15") (pinfunction "PB3(MOSI/OC2)_15") (pintype "bidirectional"))
      (node (ref "N8") (pin "3") (pinfunction "PWM-LO_3") (pintype "input"))
      (node (ref "RN9") (pin "7") (pinfunction "2_7") (pintype "passive"))
    )
    (net (code "18") (name "B-_4") (class "Default")
      (node (ref "D4") (pin "15") (pinfunction "PB3(MOSI/OC2)_15") (pintype "bidirectional"))
      (node (ref "N11") (pin "3") (pinfunction "PWM-LO_3") (pintype "input"))
      (node (ref "RN13") (pin "7") (pinfunction "2_7") (pintype "passive"))
    )
    (net (code "19") (name "C+_1") (class "Default")
      (node (ref "D1") (pin "16") (pinfunction "PB4(MISO)_16") (pintype "bidirectional"))
      (node (ref "N3") (pin "2") (pinfunction "PWM-HI_2") (pintype "input"))
    )
    (net (code "20") (name "C+_2") (class "Default")
      (node (ref "D3") (pin "16") (pinfunction "PB4(MISO)_16") (pintype "bidirectional"))
      (node (ref "N6") (pin "2") (pinfunction "PWM-HI_2") (pintype "input"))
    )
    (net (code "21") (name "C+_3") (class "Default")
      (node (ref "D2") (pin "16") (pinfunction "PB4(MISO)_16") (pintype "bidirectional"))
      (node (ref "N9") (pin "2") (pinfunction "PWM-HI_2") (pintype "input"))
    )
    (net (code "22") (name "C+_4") (class "Default")
      (node (ref "D4") (pin "16") (pinfunction "PB4(MISO)_16") (pintype "bidirectional"))
      (node (ref "N12") (pin "2") (pinfunction "PWM-HI_2") (pintype "input"))
    )
    (net (code "23") (name "C-_1") (class "Default")
      (node (ref "D1") (pin "17") (pinfunction "PB5(SCK)_17") (pintype "bidirectional"))
      (node (ref "N3") (pin "3") (pinfunction "PWM-LO_3") (pintype "input"))
      (node (ref "RN3") (pin "5") (pinfunction "2_5") (pintype "passive"))
    )
    (net (code "24") (name "C-_2") (class "Default")
      (node (ref "D3") (pin "17") (pinfunction "PB5(SCK)_17") (pintype "bidirectional"))
      (node (ref "N6") (pin "3") (pinfunction "PWM-LO_3") (pintype "input"))
      (node (ref "RN5") (pin "5") (pinfunction "2_5") (pintype "passive"))
    )
    (net (code "25") (name "C-_3") (class "Default")
      (node (ref "D2") (pin "17") (pinfunction "PB5(SCK)_17") (pintype "bidirectional"))
      (node (ref "N9") (pin "3") (pinfunction "PWM-LO_3") (pintype "input"))
      (node (ref "RN9") (pin "5") (pinfunction "2_5") (pintype "passive"))
    )
    (net (code "26") (name "C-_4") (class "Default")
      (node (ref "D4") (pin "17") (pinfunction "PB5(SCK)_17") (pintype "bidirectional"))
      (node (ref "N12") (pin "3") (pinfunction "PWM-LO_3") (pintype "input"))
      (node (ref "RN13") (pin "5") (pinfunction "2_5") (pintype "passive"))
    )
    (net (code "27") (name "GND") (class "Default")
      (node (ref "C1") (pin "2") (pinfunction "2_2") (pintype "passive"))
      (node (ref "C12") (pin "2") (pinfunction "2_2") (pintype "passive"))
      (node (ref "C14") (pin "2") (pinfunction "2_2") (pintype "passive"))
      (node (ref "C15") (pin "2") (pinfunction "2_2") (pintype "passive"))
      (node (ref "C18") (pin "2") (pinfunction "2_2") (pintype "passive"))
      (node (ref "C2") (pin "2") (pinfunction "2_2") (pintype "passive"))
      (node (ref "C20") (pin "2") (pinfunction "2_2") (pintype "passive"))
      (node (ref "C21") (pin "2") (pinfunction "2_2") (pintype "passive"))
      (node (ref "C24") (pin "2") (pinfunction "2_2") (pintype "passive"))
      (node (ref "C25") (pin "2") (pinfunction "2_2") (pintype "passive"))
      (node (ref "C26") (pin "2") (pinfunction "2_2") (pintype "passive"))
      (node (ref "C27") (pin "2") (pinfunction "2_2") (pintype "passive"))
      (node (ref "C29") (pin "2") (pinfunction "2_2") (pintype "passive"))
      (node (ref "C3") (pin "2") (pinfunction "2_2") (pintype "passive"))
      (node (ref "C30") (pin "-") (pinfunction "-_-") (pintype "passive"))
      (node (ref "C31") (pin "2") (pinfunction "2_2") (pintype "passive"))
      (node (ref "C32") (pin "2") (pinfunction "2_2") (pintype "passive"))
      (node (ref "C33") (pin "2") (pinfunction "2_2") (pintype "passive"))
      (node (ref "C34") (pin "2") (pinfunction "2_2") (pintype "passive"))
      (node (ref "C35") (pin "2") (pinfunction "2_2") (pintype "passive"))
      (node (ref "C36") (pin "2") (pinfunction "2_2") (pintype "passive"))
      (node (ref "C37") (pin "2") (pinfunction "2_2") (pintype "passive"))
      (node (ref "C38") (pin "1") (pinfunction "1_1") (pintype "passive"))
      (node (ref "C39") (pin "2") (pinfunction "2_2") (pintype "passive"))
      (node (ref "C40") (pin "2") (pinfunction "2_2") (pintype "passive"))
      (node (ref "C41") (pin "2") (pinfunction "2_2") (pintype "passive"))
      (node (ref "C42") (pin "2") (pinfunction "2_2") (pintype "passive"))
      (node (ref "C50") (pin "-") (pinfunction "-_-") (pintype "passive"))
      (node (ref "C50") (pin "-1") (pinfunction "-_-1") (pintype "passive"))
      (node (ref "C51") (pin "-") (pinfunction "-_-") (pintype "passive"))
      (node (ref "C51") (pin "-1") (pinfunction "-_-1") (pintype "passive"))
      (node (ref "C52") (pin "-") (pinfunction "-_-") (pintype "passive"))
      (node (ref "C52") (pin "-1") (pinfunction "-_-1") (pintype "passive"))
      (node (ref "C53") (pin "-") (pinfunction "-_-") (pintype "passive"))
      (node (ref "C53") (pin "-1") (pinfunction "-_-1") (pintype "passive"))
      (node (ref "C54") (pin "-") (pinfunction "-_-") (pintype "passive"))
      (node (ref "C54") (pin "-1") (pinfunction "-_-1") (pintype "passive"))
      (node (ref "C55") (pin "-") (pinfunction "-_-") (pintype "passive"))
      (node (ref "C55") (pin "-1") (pinfunction "-_-1") (pintype "passive"))
      (node (ref "C56") (pin "-") (pinfunction "-_-") (pintype "passive"))
      (node (ref "C56") (pin "-1") (pinfunction "-_-1") (pintype "passive"))
      (node (ref "C8") (pin "2") (pinfunction "2_2") (pintype "passive"))
      (node (ref "C9") (pin "2") (pinfunction "2_2") (pintype "passive"))
      (node (ref "D1") (pin "21") (pinfunction "GND_21") (pintype "power_in"))
      (node (ref "D1") (pin "3") (pinfunction "GND_3") (pintype "power_in"))
      (node (ref "D1") (pin "5") (pinfunction "GND_5") (pintype "power_in"))
      (node (ref "D2") (pin "21") (pinfunction "GND_21") (pintype "power_in"))
      (node (ref "D2") (pin "3") (pinfunction "GND_3") (pintype "power_in"))
      (node (ref "D2") (pin "5") (pinfunction "GND_5") (pintype "power_in"))
      (node (ref "D3") (pin "21") (pinfunction "GND_21") (pintype "power_in"))
      (node (ref "D3") (pin "3") (pinfunction "GND_3") (pintype "power_in"))
      (node (ref "D3") (pin "5") (pinfunction "GND_5") (pintype "power_in"))
      (node (ref "D4") (pin "21") (pinfunction "GND_21") (pintype "power_in"))
      (node (ref "D4") (pin "3") (pinfunction "GND_3") (pintype "power_in"))
      (node (ref "D4") (pin "5") (pinfunction "GND_5") (pintype "power_in"))
      (node (ref "H1") (pin "C") (pinfunction "C_C") (pintype "passive"))
      (node (ref "H2") (pin "C") (pinfunction "C_C") (pintype "passive"))
      (node (ref "H3") (pin "C") (pinfunction "C_C") (pintype "passive"))
      (node (ref "H4") (pin "C") (pinfunction "C_C") (pintype "passive"))
      (node (ref "H5") (pin "C") (pinfunction "C_C") (pintype "passive"))
      (node (ref "H6") (pin "C") (pinfunction "C_C") (pintype "passive"))
      (node (ref "H7") (pin "C") (pinfunction "C_C") (pintype "passive"))
      (node (ref "H8") (pin "C") (pinfunction "C_C") (pintype "passive"))
      (node (ref "H9") (pin "C") (pinfunction "C_C") (pintype "passive"))
      (node (ref "JP1") (pin "1") (pinfunction "1_1") (pintype "passive"))
      (node (ref "JP2") (pin "1") (pinfunction "1_1") (pintype "passive"))
      (node (ref "N1") (pin "4") (pinfunction "GND_4") (pintype "power_in"))
      (node (ref "N10") (pin "4") (pinfunction "GND_4") (pintype "power_in"))
      (node (ref "N11") (pin "4") (pinfunction "GND_4") (pintype "power_in"))
      (node (ref "N12") (pin "4") (pinfunction "GND_4") (pintype "power_in"))
      (node (ref "N2") (pin "4") (pinfunction "GND_4") (pintype "power_in"))
      (node (ref "N3") (pin "4") (pinfunction "GND_4") (pintype "power_in"))
      (node (ref "N4") (pin "4") (pinfunction "GND_4") (pintype "power_in"))
      (node (ref "N5") (pin "4") (pinfunction "GND_4") (pintype "power_in"))
      (node (ref "N6") (pin "4") (pinfunction "GND_4") (pintype "power_in"))
      (node (ref "N7") (pin "4") (pinfunction "GND_4") (pintype "power_in"))
      (node (ref "N8") (pin "4") (pinfunction "GND_4") (pintype "power_in"))
      (node (ref "N9") (pin "4") (pinfunction "GND_4") (pintype "power_in"))
      (node (ref "Q1") (pin "2") (pinfunction "2_2") (pintype "passive"))
      (node (ref "Q2") (pin "2") (pinfunction "2_2") (pintype "passive"))
      (node (ref "Q3") (pin "2") (pinfunction "2_2") (pintype "passive"))
      (node (ref "Q4") (pin "2") (pinfunction "2_2") (pintype "passive"))
      (node (ref "R46") (pin "1") (pinfunction "1_1") (pintype "passive"))
      (node (ref "RN11") (pin "1") (pinfunction "1_1") (pintype "passive"))
      (node (ref "RN11") (pin "2") (pinfunction "1_2") (pintype "passive"))
      (node (ref "RN11") (pin "3") (pinfunction "1_3") (pintype "passive"))
      (node (ref "RN11") (pin "4") (pinfunction "1_4") (pintype "passive"))
      (node (ref "RN13") (pin "1") (pinfunction "1_1") (pintype "passive"))
      (node (ref "RN13") (pin "2") (pinfunction "1_2") (pintype "passive"))
      (node (ref "RN13") (pin "3") (pinfunction "1_3") (pintype "passive"))
      (node (ref "RN13") (pin "4") (pinfunction "1_4") (pintype "passive"))
      (node (ref "RN15") (pin "1") (pinfunction "1_1") (pintype "passive"))
      (node (ref "RN15") (pin "2") (pinfunction "1_2") (pintype "passive"))
      (node (ref "RN15") (pin "3") (pinfunction "1_3") (pintype "passive"))
      (node (ref "RN15") (pin "4") (pinfunction "1_4") (pintype "passive"))
      (node (ref "RN3") (pin "1") (pinfunction "1_1") (pintype "passive"))
      (node (ref "RN3") (pin "2") (pinfunction "1_2") (pintype "passive"))
      (node (ref "RN3") (pin "3") (pinfunction "1_3") (pintype "passive"))
      (node (ref "RN3") (pin "4") (pinfunction "1_4") (pintype "passive"))
      (node (ref "RN4") (pin "1") (pinfunction "1_1") (pintype "passive"))
      (node (ref "RN4") (pin "2") (pinfunction "1_2") (pintype "passive"))
      (node (ref "RN4") (pin "3") (pinfunction "1_3") (pintype "passive"))
      (node (ref "RN4") (pin "4") (pinfunction "1_4") (pintype "passive"))
      (node (ref "RN5") (pin "1") (pinfunction "1_1") (pintype "passive"))
      (node (ref "RN5") (pin "2") (pinfunction "1_2") (pintype "passive"))
      (node (ref "RN5") (pin "3") (pinfunction "1_3") (pintype "passive"))
      (node (ref "RN5") (pin "4") (pinfunction "1_4") (pintype "passive"))
      (node (ref "RN7") (pin "1") (pinfunction "1_1") (pintype "passive"))
      (node (ref "RN7") (pin "2") (pinfunction "1_2") (pintype "passive"))
      (node (ref "RN7") (pin "3") (pinfunction "1_3") (pintype "passive"))
      (node (ref "RN7") (pin "4") (pinfunction "1_4") (pintype "passive"))
      (node (ref "RN9") (pin "1") (pinfunction "1_1") (pintype "passive"))
      (node (ref "RN9") (pin "2") (pinfunction "1_2") (pintype "passive"))
      (node (ref "RN9") (pin "3") (pinfunction "1_3") (pintype "passive"))
      (node (ref "RN9") (pin "4") (pinfunction "1_4") (pintype "passive"))
      (node (ref "U1") (pin "2") (pinfunction "GND_2") (pintype "bidirectional"))
      (node (ref "V10") (pin "P$1") (pinfunction "S_P$1") (pintype "passive"))
      (node (ref "V10") (pin "P$2") (pinfunction "S_P$2") (pintype "passive"))
      (node (ref "V10") (pin "P$3") (pinfunction "S_P$3") (pintype "passive"))
      (node (ref "V12") (pin "P$1") (pinfunction "S_P$1") (pintype "passive"))
      (node (ref "V12") (pin "P$2") (pinfunction "S_P$2") (pintype "passive"))
      (node (ref "V12") (pin "P$3") (pinfunction "S_P$3") (pintype "passive"))
      (node (ref "V14") (pin "P$1") (pinfunction "S_P$1") (pintype "passive"))
      (node (ref "V14") (pin "P$2") (pinfunction "S_P$2") (pintype "passive"))
      (node (ref "V14") (pin "P$3") (pinfunction "S_P$3") (pintype "passive"))
      (node (ref "V16") (pin "P$1") (pinfunction "S_P$1") (pintype "passive"))
      (node (ref "V16") (pin "P$2") (pinfunction "S_P$2") (pintype "passive"))
      (node (ref "V16") (pin "P$3") (pinfunction "S_P$3") (pintype "passive"))
      (node (ref "V18") (pin "P$1") (pinfunction "S_P$1") (pintype "passive"))
      (node (ref "V18") (pin "P$2") (pinfunction "S_P$2") (pintype "passive"))
      (node (ref "V18") (pin "P$3") (pinfunction "S_P$3") (pintype "passive"))
      (node (ref "V2") (pin "P$1") (pinfunction "S_P$1") (pintype "passive"))
      (node (ref "V2") (pin "P$2") (pinfunction "S_P$2") (pintype "passive"))
      (node (ref "V2") (pin "P$3") (pinfunction "S_P$3") (pintype "passive"))
      (node (ref "V20") (pin "P$1") (pinfunction "S_P$1") (pintype "passive"))
      (node (ref "V20") (pin "P$2") (pinfunction "S_P$2") (pintype "passive"))
      (node (ref "V20") (pin "P$3") (pinfunction "S_P$3") (pintype "passive"))
      (node (ref "V22") (pin "P$1") (pinfunction "S_P$1") (pintype "passive"))
      (node (ref "V22") (pin "P$2") (pinfunction "S_P$2") (pintype "passive"))
      (node (ref "V22") (pin "P$3") (pinfunction "S_P$3") (pintype "passive"))
      (node (ref "V24") (pin "P$1") (pinfunction "S_P$1") (pintype "passive"))
      (node (ref "V24") (pin "P$2") (pinfunction "S_P$2") (pintype "passive"))
      (node (ref "V24") (pin "P$3") (pinfunction "S_P$3") (pintype "passive"))
      (node (ref "V26") (pin "A") (pinfunction "A_A") (pintype "passive"))
      (node (ref "V4") (pin "P$1") (pinfunction "S_P$1") (pintype "passive"))
      (node (ref "V4") (pin "P$2") (pinfunction "S_P$2") (pintype "passive"))
      (node (ref "V4") (pin "P$3") (pinfunction "S_P$3") (pintype "passive"))
      (node (ref "V6") (pin "P$1") (pinfunction "S_P$1") (pintype "passive"))
      (node (ref "V6") (pin "P$2") (pinfunction "S_P$2") (pintype "passive"))
      (node (ref "V6") (pin "P$3") (pinfunction "S_P$3") (pintype "passive"))
      (node (ref "V8") (pin "P$1") (pinfunction "S_P$1") (pintype "passive"))
      (node (ref "V8") (pin "P$2") (pinfunction "S_P$2") (pintype "passive"))
      (node (ref "V8") (pin "P$3") (pinfunction "S_P$3") (pintype "passive"))
      (node (ref "X1") (pin "6") (pinfunction "S_6") (pintype "passive"))
      (node (ref "X2") (pin "1") (pinfunction "S_1") (pintype "passive"))
    )
    (net (code "28") (name "GREEN_LED_1") (class "Default")
      (node (ref "D1") (pin "2") (pinfunction "PD4(XCK/T0)_2") (pintype "bidirectional"))
      (node (ref "RN1") (pin "4") (pinfunction "1_4") (pintype "passive"))
    )
    (net (code "29") (name "GREEN_LED_2") (class "Default")
      (node (ref "D3") (pin "2") (pinfunction "PD4(XCK/T0)_2") (pintype "bidirectional"))
      (node (ref "RN6") (pin "4") (pinfunction "1_4") (pintype "passive"))
    )
    (net (code "30") (name "GREEN_LED_3") (class "Default")
      (node (ref "D2") (pin "2") (pinfunction "PD4(XCK/T0)_2") (pintype "bidirectional"))
      (node (ref "RN10") (pin "4") (pinfunction "1_4") (pintype "passive"))
    )
    (net (code "31") (name "GREEN_LED_4") (class "Default")
      (node (ref "D4") (pin "2") (pinfunction "PD4(XCK/T0)_2") (pintype "bidirectional"))
      (node (ref "RN14") (pin "4") (pinfunction "1_4") (pintype "passive"))
    )
    (net (code "32") (name "MOTOR-A_1") (class "Default")
      (node (ref "C4") (pin "2") (pinfunction "2_2") (pintype "passive"))
      (node (ref "N1") (pin "1") (pinfunction "PHASE_1") (pintype "output"))
      (node (ref "R3") (pin "2") (pinfunction "2_2") (pintype "passive"))
      (node (ref "V1") (pin "P$1") (pinfunction "S_P$1") (pintype "passive"))
      (node (ref "V1") (pin "P$2") (pinfunction "S_P$2") (pintype "passive"))
      (node (ref "V1") (pin "P$3") (pinfunction "S_P$3") (pintype "passive"))
      (node (ref "V2") (pin "P$5") (pinfunction "D_P$5") (pintype "passive"))
      (node (ref "V2") (pin "P$6") (pinfunction "D_P$6") (pintype "passive"))
      (node (ref "V2") (pin "P$7") (pinfunction "D_P$7") (pintype "passive"))
      (node (ref "V2") (pin "P$8") (pinfunction "D_P$8") (pintype "passive"))
      (node (ref "V2") (pin "P$9") (pinfunction "D_P$9") (pintype "passive"))
    )
    (net (code "33") (name "MOTOR-A_2") (class "Default")
      (node (ref "C7") (pin "2") (pinfunction "2_2") (pintype "passive"))
      (node (ref "N4") (pin "1") (pinfunction "PHASE_1") (pintype "output"))
      (node (ref "R14") (pin "2") (pinfunction "2_2") (pintype "passive"))
      (node (ref "V7") (pin "P$1") (pinfunction "S_P$1") (pintype "passive"))
      (node (ref "V7") (pin "P$2") (pinfunction "S_P$2") (pintype "passive"))
      (node (ref "V7") (pin "P$3") (pinfunction "S_P$3") (pintype "passive"))
      (node (ref "V8") (pin "P$5") (pinfunction "D_P$5") (pintype "passive"))
      (node (ref "V8") (pin "P$6") (pinfunction "D_P$6") (pintype "passive"))
      (node (ref "V8") (pin "P$7") (pinfunction "D_P$7") (pintype "passive"))
      (node (ref "V8") (pin "P$8") (pinfunction "D_P$8") (pintype "passive"))
      (node (ref "V8") (pin "P$9") (pinfunction "D_P$9") (pintype "passive"))
    )
    (net (code "34") (name "MOTOR-A_3") (class "Default")
      (node (ref "C13") (pin "2") (pinfunction "2_2") (pintype "passive"))
      (node (ref "N7") (pin "1") (pinfunction "PHASE_1") (pintype "output"))
      (node (ref "R25") (pin "2") (pinfunction "2_2") (pintype "passive"))
      (node (ref "V13") (pin "P$1") (pinfunction "S_P$1") (pintype "passive"))
      (node (ref "V13") (pin "P$2") (pinfunction "S_P$2") (pintype "passive"))
      (node (ref "V13") (pin "P$3") (pinfunction "S_P$3") (pintype "passive"))
      (node (ref "V14") (pin "P$5") (pinfunction "D_P$5") (pintype "passive"))
      (node (ref "V14") (pin "P$6") (pinfunction "D_P$6") (pintype "passive"))
      (node (ref "V14") (pin "P$7") (pinfunction "D_P$7") (pintype "passive"))
      (node (ref "V14") (pin "P$8") (pinfunction "D_P$8") (pintype "passive"))
      (node (ref "V14") (pin "P$9") (pinfunction "D_P$9") (pintype "passive"))
    )
    (net (code "35") (name "MOTOR-A_4") (class "Default")
      (node (ref "C19") (pin "2") (pinfunction "2_2") (pintype "passive"))
      (node (ref "N10") (pin "1") (pinfunction "PHASE_1") (pintype "output"))
      (node (ref "R36") (pin "2") (pinfunction "2_2") (pintype "passive"))
      (node (ref "V19") (pin "P$1") (pinfunction "S_P$1") (pintype "passive"))
      (node (ref "V19") (pin "P$2") (pinfunction "S_P$2") (pintype "passive"))
      (node (ref "V19") (pin "P$3") (pinfunction "S_P$3") (pintype "passive"))
      (node (ref "V20") (pin "P$5") (pinfunction "D_P$5") (pintype "passive"))
      (node (ref "V20") (pin "P$6") (pinfunction "D_P$6") (pintype "passive"))
      (node (ref "V20") (pin "P$7") (pinfunction "D_P$7") (pintype "passive"))
      (node (ref "V20") (pin "P$8") (pinfunction "D_P$8") (pintype "passive"))
      (node (ref "V20") (pin "P$9") (pinfunction "D_P$9") (pintype "passive"))
    )
    (net (code "36") (name "MOTOR-B_1") (class "Default")
      (node (ref "C5") (pin "2") (pinfunction "2_2") (pintype "passive"))
      (node (ref "N2") (pin "1") (pinfunction "PHASE_1") (pintype "output"))
      (node (ref "R4") (pin "2") (pinfunction "2_2") (pintype "passive"))
      (node (ref "V3") (pin "P$1") (pinfunction "S_P$1") (pintype "passive"))
      (node (ref "V3") (pin "P$2") (pinfunction "S_P$2") (pintype "passive"))
      (node (ref "V3") (pin "P$3") (pinfunction "S_P$3") (pintype "passive"))
      (node (ref "V4") (pin "P$5") (pinfunction "D_P$5") (pintype "passive"))
      (node (ref "V4") (pin "P$6") (pinfunction "D_P$6") (pintype "passive"))
      (node (ref "V4") (pin "P$7") (pinfunction "D_P$7") (pintype "passive"))
      (node (ref "V4") (pin "P$8") (pinfunction "D_P$8") (pintype "passive"))
      (node (ref "V4") (pin "P$9") (pinfunction "D_P$9") (pintype "passive"))
    )
    (net (code "37") (name "MOTOR-B_2") (class "Default")
      (node (ref "C10") (pin "2") (pinfunction "2_2") (pintype "passive"))
      (node (ref "N5") (pin "1") (pinfunction "PHASE_1") (pintype "output"))
      (node (ref "R17") (pin "2") (pinfunction "2_2") (pintype "passive"))
      (node (ref "V10") (pin "P$5") (pinfunction "D_P$5") (pintype "passive"))
      (node (ref "V10") (pin "P$6") (pinfunction "D_P$6") (pintype "passive"))
      (node (ref "V10") (pin "P$7") (pinfunction "D_P$7") (pintype "passive"))
      (node (ref "V10") (pin "P$8") (pinfunction "D_P$8") (pintype "passive"))
      (node (ref "V10") (pin "P$9") (pinfunction "D_P$9") (pintype "passive"))
      (node (ref "V9") (pin "P$1") (pinfunction "S_P$1") (pintype "passive"))
      (node (ref "V9") (pin "P$2") (pinfunction "S_P$2") (pintype "passive"))
      (node (ref "V9") (pin "P$3") (pinfunction "S_P$3") (pintype "passive"))
    )
    (net (code "38") (name "MOTOR-B_3") (class "Default")
      (node (ref "C16") (pin "2") (pinfunction "2_2") (pintype "passive"))
      (node (ref "N8") (pin "1") (pinfunction "PHASE_1") (pintype "output"))
      (node (ref "R28") (pin "2") (pinfunction "2_2") (pintype "passive"))
      (node (ref "V15") (pin "P$1") (pinfunction "S_P$1") (pintype "passive"))
      (node (ref "V15") (pin "P$2") (pinfunction "S_P$2") (pintype "passive"))
      (node (ref "V15") (pin "P$3") (pinfunction "S_P$3") (pintype "passive"))
      (node (ref "V16") (pin "P$5") (pinfunction "D_P$5") (pintype "passive"))
      (node (ref "V16") (pin "P$6") (pinfunction "D_P$6") (pintype "passive"))
      (node (ref "V16") (pin "P$7") (pinfunction "D_P$7") (pintype "passive"))
      (node (ref "V16") (pin "P$8") (pinfunction "D_P$8") (pintype "passive"))
      (node (ref "V16") (pin "P$9") (pinfunction "D_P$9") (pintype "passive"))
    )
    (net (code "39") (name "MOTOR-B_4") (class "Default")
      (node (ref "C22") (pin "2") (pinfunction "2_2") (pintype "passive"))
      (node (ref "N11") (pin "1") (pinfunction "PHASE_1") (pintype "output"))
      (node (ref "R39") (pin "2") (pinfunction "2_2") (pintype "passive"))
      (node (ref "V21") (pin "P$1") (pinfunction "S_P$1") (pintype "passive"))
      (node (ref "V21") (pin "P$2") (pinfunction "S_P$2") (pintype "passive"))
      (node (ref "V21") (pin "P$3") (pinfunction "S_P$3") (pintype "passive"))
      (node (ref "V22") (pin "P$5") (pinfunction "D_P$5") (pintype "passive"))
      (node (ref "V22") (pin "P$6") (pinfunction "D_P$6") (pintype "passive"))
      (node (ref "V22") (pin "P$7") (pinfunction "D_P$7") (pintype "passive"))
      (node (ref "V22") (pin "P$8") (pinfunction "D_P$8") (pintype "passive"))
      (node (ref "V22") (pin "P$9") (pinfunction "D_P$9") (pintype "passive"))
    )
    (net (code "40") (name "MOTOR-C_1") (class "Default")
      (node (ref "C6") (pin "2") (pinfunction "2_2") (pintype "passive"))
      (node (ref "N3") (pin "1") (pinfunction "PHASE_1") (pintype "output"))
      (node (ref "R5") (pin "2") (pinfunction "2_2") (pintype "passive"))
      (node (ref "V5") (pin "P$1") (pinfunction "S_P$1") (pintype "passive"))
      (node (ref "V5") (pin "P$2") (pinfunction "S_P$2") (pintype "passive"))
      (node (ref "V5") (pin "P$3") (pinfunction "S_P$3") (pintype "passive"))
      (node (ref "V6") (pin "P$5") (pinfunction "D_P$5") (pintype "passive"))
      (node (ref "V6") (pin "P$6") (pinfunction "D_P$6") (pintype "passive"))
      (node (ref "V6") (pin "P$7") (pinfunction "D_P$7") (pintype "passive"))
      (node (ref "V6") (pin "P$8") (pinfunction "D_P$8") (pintype "passive"))
      (node (ref "V6") (pin "P$9") (pinfunction "D_P$9") (pintype "passive"))
    )
    (net (code "41") (name "MOTOR-C_2") (class "Default")
      (node (ref "C11") (pin "2") (pinfunction "2_2") (pintype "passive"))
      (node (ref "N6") (pin "1") (pinfunction "PHASE_1") (pintype "output"))
      (node (ref "R20") (pin "2") (pinfunction "2_2") (pintype "passive"))
      (node (ref "V11") (pin "P$1") (pinfunction "S_P$1") (pintype "passive"))
      (node (ref "V11") (pin "P$2") (pinfunction "S_P$2") (pintype "passive"))
      (node (ref "V11") (pin "P$3") (pinfunction "S_P$3") (pintype "passive"))
      (node (ref "V12") (pin "P$5") (pinfunction "D_P$5") (pintype "passive"))
      (node (ref "V12") (pin "P$6") (pinfunction "D_P$6") (pintype "passive"))
      (node (ref "V12") (pin "P$7") (pinfunction "D_P$7") (pintype "passive"))
      (node (ref "V12") (pin "P$8") (pinfunction "D_P$8") (pintype "passive"))
      (node (ref "V12") (pin "P$9") (pinfunction "D_P$9") (pintype "passive"))
    )
    (net (code "42") (name "MOTOR-C_3") (class "Default")
      (node (ref "C17") (pin "2") (pinfunction "2_2") (pintype "passive"))
      (node (ref "N9") (pin "1") (pinfunction "PHASE_1") (pintype "output"))
      (node (ref "R31") (pin "2") (pinfunction "2_2") (pintype "passive"))
      (node (ref "V17") (pin "P$1") (pinfunction "S_P$1") (pintype "passive"))
      (node (ref "V17") (pin "P$2") (pinfunction "S_P$2") (pintype "passive"))
      (node (ref "V17") (pin "P$3") (pinfunction "S_P$3") (pintype "passive"))
      (node (ref "V18") (pin "P$5") (pinfunction "D_P$5") (pintype "passive"))
      (node (ref "V18") (pin "P$6") (pinfunction "D_P$6") (pintype "passive"))
      (node (ref "V18") (pin "P$7") (pinfunction "D_P$7") (pintype "passive"))
      (node (ref "V18") (pin "P$8") (pinfunction "D_P$8") (pintype "passive"))
      (node (ref "V18") (pin "P$9") (pinfunction "D_P$9") (pintype "passive"))
    )
    (net (code "43") (name "MOTOR-C_4") (class "Default")
      (node (ref "C23") (pin "2") (pinfunction "2_2") (pintype "passive"))
      (node (ref "N12") (pin "1") (pinfunction "PHASE_1") (pintype "output"))
      (node (ref "R42") (pin "2") (pinfunction "2_2") (pintype "passive"))
      (node (ref "V23") (pin "P$1") (pinfunction "S_P$1") (pintype "passive"))
      (node (ref "V23") (pin "P$2") (pinfunction "S_P$2") (pintype "passive"))
      (node (ref "V23") (pin "P$3") (pinfunction "S_P$3") (pintype "passive"))
      (node (ref "V24") (pin "P$5") (pinfunction "D_P$5") (pintype "passive"))
      (node (ref "V24") (pin "P$6") (pinfunction "D_P$6") (pintype "passive"))
      (node (ref "V24") (pin "P$7") (pinfunction "D_P$7") (pintype "passive"))
      (node (ref "V24") (pin "P$8") (pinfunction "D_P$8") (pintype "passive"))
      (node (ref "V24") (pin "P$9") (pinfunction "D_P$9") (pintype "passive"))
    )
    (net (code "44") (name "MUXA_1") (class "Default")
      (node (ref "D1") (pin "26") (pinfunction "PC3(ADC3)_26") (pintype "bidirectional"))
      (node (ref "R3") (pin "1") (pinfunction "1_1") (pintype "passive"))
      (node (ref "RN2") (pin "8") (pinfunction "2_8") (pintype "passive"))
      (node (ref "RN4") (pin "8") (pinfunction "2_8") (pintype "passive"))
    )
    (net (code "45") (name "MUXA_2") (class "Default")
      (node (ref "D3") (pin "26") (pinfunction "PC3(ADC3)_26") (pintype "bidirectional"))
      (node (ref "R14") (pin "1") (pinfunction "1_1") (pintype "passive"))
      (node (ref "RN7") (pin "8") (pinfunction "2_8") (pintype "passive"))
      (node (ref "RN8") (pin "8") (pinfunction "2_8") (pintype "passive"))
    )
    (net (code "46") (name "MUXA_3") (class "Default")
      (node (ref "D2") (pin "26") (pinfunction "PC3(ADC3)_26") (pintype "bidirectional"))
      (node (ref "R25") (pin "1") (pinfunction "1_1") (pintype "passive"))
      (node (ref "RN11") (pin "8") (pinfunction "2_8") (pintype "passive"))
      (node (ref "RN12") (pin "8") (pinfunction "2_8") (pintype "passive"))
    )
    (net (code "47") (name "MUXA_4") (class "Default")
      (node (ref "D4") (pin "26") (pinfunction "PC3(ADC3)_26") (pintype "bidirectional"))
      (node (ref "R36") (pin "1") (pinfunction "1_1") (pintype "passive"))
      (node (ref "RN15") (pin "8") (pinfunction "2_8") (pintype "passive"))
      (node (ref "RN16") (pin "8") (pinfunction "2_8") (pintype "passive"))
    )
    (net (code "48") (name "MUXB_1") (class "Default")
      (node (ref "D1") (pin "25") (pinfunction "PC2(ADC2)_25") (pintype "bidirectional"))
      (node (ref "R4") (pin "1") (pinfunction "1_1") (pintype "passive"))
      (node (ref "RN2") (pin "7") (pinfunction "2_7") (pintype "passive"))
      (node (ref "RN4") (pin "7") (pinfunction "2_7") (pintype "passive"))
    )
    (net (code "49") (name "MUXB_2") (class "Default")
      (node (ref "D3") (pin "25") (pinfunction "PC2(ADC2)_25") (pintype "bidirectional"))
      (node (ref "R17") (pin "1") (pinfunction "1_1") (pintype "passive"))
      (node (ref "RN7") (pin "7") (pinfunction "2_7") (pintype "passive"))
      (node (ref "RN8") (pin "7") (pinfunction "2_7") (pintype "passive"))
    )
    (net (code "50") (name "MUXB_3") (class "Default")
      (node (ref "D2") (pin "25") (pinfunction "PC2(ADC2)_25") (pintype "bidirectional"))
      (node (ref "R28") (pin "1") (pinfunction "1_1") (pintype "passive"))
      (node (ref "RN11") (pin "7") (pinfunction "2_7") (pintype "passive"))
      (node (ref "RN12") (pin "7") (pinfunction "2_7") (pintype "passive"))
    )
    (net (code "51") (name "MUXB_4") (class "Default")
      (node (ref "D4") (pin "25") (pinfunction "PC2(ADC2)_25") (pintype "bidirectional"))
      (node (ref "R39") (pin "1") (pinfunction "1_1") (pintype "passive"))
      (node (ref "RN15") (pin "7") (pinfunction "2_7") (pintype "passive"))
      (node (ref "RN16") (pin "7") (pinfunction "2_7") (pintype "passive"))
    )
    (net (code "52") (name "MUXC_1") (class "Default")
      (node (ref "D1") (pin "24") (pinfunction "PC1(ADC1)_24") (pintype "bidirectional"))
      (node (ref "R5") (pin "1") (pinfunction "1_1") (pintype "passive"))
      (node (ref "RN2") (pin "5") (pinfunction "2_5") (pintype "passive"))
      (node (ref "RN4") (pin "5") (pinfunction "2_5") (pintype "passive"))
    )
    (net (code "53") (name "MUXC_2") (class "Default")
      (node (ref "D3") (pin "24") (pinfunction "PC1(ADC1)_24") (pintype "bidirectional"))
      (node (ref "R20") (pin "1") (pinfunction "1_1") (pintype "passive"))
      (node (ref "RN7") (pin "5") (pinfunction "2_5") (pintype "passive"))
      (node (ref "RN8") (pin "5") (pinfunction "2_5") (pintype "passive"))
    )
    (net (code "54") (name "MUXC_3") (class "Default")
      (node (ref "D2") (pin "24") (pinfunction "PC1(ADC1)_24") (pintype "bidirectional"))
      (node (ref "R31") (pin "1") (pinfunction "1_1") (pintype "passive"))
      (node (ref "RN11") (pin "5") (pinfunction "2_5") (pintype "passive"))
      (node (ref "RN12") (pin "5") (pinfunction "2_5") (pintype "passive"))
    )
    (net (code "55") (name "MUXC_4") (class "Default")
      (node (ref "D4") (pin "24") (pinfunction "PC1(ADC1)_24") (pintype "bidirectional"))
      (node (ref "R42") (pin "1") (pinfunction "1_1") (pintype "passive"))
      (node (ref "RN15") (pin "5") (pinfunction "2_5") (pintype "passive"))
      (node (ref "RN16") (pin "5") (pinfunction "2_5") (pintype "passive"))
    )
    (net (code "56") (name "N$8") (class "Default")
      (node (ref "C27") (pin "1") (pinfunction "1_1") (pintype "passive"))
      (node (ref "D1") (pin "20") (pinfunction "AREF_20") (pintype "passive"))
    )
    (net (code "57") (name "N$10") (class "Default")
      (node (ref "D1") (pin "9") (pinfunction "PD5(T1)_9") (pintype "bidirectional"))
    )
    (net (code "58") (name "N$11") (class "Default")
      (node (ref "D1") (pin "23") (pinfunction "PC0(ADC0)_23") (pintype "bidirectional"))
    )
    (net (code "59") (name "N$12") (class "Default")
      (node (ref "D1") (pin "22") (pinfunction "ADC7_22") (pintype "bidirectional"))
    )
    (net (code "60") (name "N$13") (class "Default")
      (node (ref "D1") (pin "19") (pinfunction "ADC6_19") (pintype "bidirectional"))
    )
    (net (code "61") (name "N$15") (class "Default")
      (node (ref "D1") (pin "30") (pinfunction "PD0(RXD)_30") (pintype "bidirectional"))
    )
    (net (code "62") (name "N$18") (class "Default")
      (node (ref "D1") (pin "31") (pinfunction "PD1(TXD)_31") (pintype "bidirectional"))
    )
    (net (code "63") (name "N$19") (class "Default")
      (node (ref "D1") (pin "11") (pinfunction "PD7(AIN1)_11") (pintype "bidirectional"))
    )
    (net (code "64") (name "N$21") (class "Default")
      (node (ref "D3") (pin "9") (pinfunction "PD5(T1)_9") (pintype "bidirectional"))
    )
    (net (code "65") (name "N$22") (class "Default")
      (node (ref "D3") (pin "23") (pinfunction "PC0(ADC0)_23") (pintype "bidirectional"))
    )
    (net (code "66") (name "N$23") (class "Default")
      (node (ref "D3") (pin "22") (pinfunction "ADC7_22") (pintype "bidirectional"))
    )
    (net (code "67") (name "N$24") (class "Default")
      (node (ref "D3") (pin "19") (pinfunction "ADC6_19") (pintype "bidirectional"))
    )
    (net (code "68") (name "N$25") (class "Default")
      (node (ref "D3") (pin "30") (pinfunction "PD0(RXD)_30") (pintype "bidirectional"))
    )
    (net (code "69") (name "N$26") (class "Default")
      (node (ref "D3") (pin "31") (pinfunction "PD1(TXD)_31") (pintype "bidirectional"))
    )
    (net (code "70") (name "N$27") (class "Default")
      (node (ref "D3") (pin "11") (pinfunction "PD7(AIN1)_11") (pintype "bidirectional"))
    )
    (net (code "71") (name "N$35") (class "Default")
      (node (ref "D2") (pin "9") (pinfunction "PD5(T1)_9") (pintype "bidirectional"))
    )
    (net (code "72") (name "N$36") (class "Default")
      (node (ref "D2") (pin "23") (pinfunction "PC0(ADC0)_23") (pintype "bidirectional"))
    )
    (net (code "73") (name "N$37") (class "Default")
      (node (ref "D2") (pin "22") (pinfunction "ADC7_22") (pintype "bidirectional"))
    )
    (net (code "74") (name "N$38") (class "Default")
      (node (ref "D2") (pin "19") (pinfunction "ADC6_19") (pintype "bidirectional"))
    )
    (net (code "75") (name "N$39") (class "Default")
      (node (ref "D2") (pin "30") (pinfunction "PD0(RXD)_30") (pintype "bidirectional"))
    )
    (net (code "76") (name "N$40") (class "Default")
      (node (ref "D2") (pin "31") (pinfunction "PD1(TXD)_31") (pintype "bidirectional"))
    )
    (net (code "77") (name "N$41") (class "Default")
      (node (ref "D2") (pin "11") (pinfunction "PD7(AIN1)_11") (pintype "bidirectional"))
    )
    (net (code "78") (name "N$49") (class "Default")
      (node (ref "D4") (pin "9") (pinfunction "PD5(T1)_9") (pintype "bidirectional"))
    )
    (net (code "79") (name "N$50") (class "Default")
      (node (ref "D4") (pin "23") (pinfunction "PC0(ADC0)_23") (pintype "bidirectional"))
    )
    (net (code "80") (name "N$51") (class "Default")
      (node (ref "D4") (pin "22") (pinfunction "ADC7_22") (pintype "bidirectional"))
    )
    (net (code "81") (name "N$52") (class "Default")
      (node (ref "D4") (pin "19") (pinfunction "ADC6_19") (pintype "bidirectional"))
    )
    (net (code "82") (name "N$53") (class "Default")
      (node (ref "D4") (pin "30") (pinfunction "PD0(RXD)_30") (pintype "bidirectional"))
    )
    (net (code "83") (name "N$54") (class "Default")
      (node (ref "D4") (pin "31") (pinfunction "PD1(TXD)_31") (pintype "bidirectional"))
    )
    (net (code "84") (name "N$55") (class "Default")
      (node (ref "D4") (pin "11") (pinfunction "PD7(AIN1)_11") (pintype "bidirectional"))
    )
    (net (code "85") (name "Net-(D1-PB6(XTAL1{slash}TOSC1))") (class "Default")
      (node (ref "D1") (pin "7") (pinfunction "PB6(XTAL1/TOSC1)_7") (pintype "bidirectional"))
      (node (ref "Q1") (pin "1") (pinfunction "1_1") (pintype "passive"))
    )
    (net (code "86") (name "Net-(D1-PB7(XTAL2{slash}TOSC2))") (class "Default")
      (node (ref "D1") (pin "8") (pinfunction "PB7(XTAL2/TOSC2)_8") (pintype "bidirectional"))
      (node (ref "Q1") (pin "3") (pinfunction "3_3") (pintype "passive"))
    )
    (net (code "87") (name "Net-(D2-AREF)") (class "Default")
      (node (ref "C40") (pin "1") (pinfunction "1_1") (pintype "passive"))
      (node (ref "D2") (pin "20") (pinfunction "AREF_20") (pintype "passive"))
    )
    (net (code "88") (name "Net-(D2-PB6(XTAL1{slash}TOSC1))") (class "Default")
      (node (ref "D2") (pin "7") (pinfunction "PB6(XTAL1/TOSC1)_7") (pintype "bidirectional"))
      (node (ref "Q3") (pin "1") (pinfunction "1_1") (pintype "passive"))
    )
    (net (code "89") (name "Net-(D2-PB7(XTAL2{slash}TOSC2))") (class "Default")
      (node (ref "D2") (pin "8") (pinfunction "PB7(XTAL2/TOSC2)_8") (pintype "bidirectional"))
      (node (ref "Q3") (pin "3") (pinfunction "3_3") (pintype "passive"))
    )
    (net (code "90") (name "Net-(D3-AREF)") (class "Default")
      (node (ref "C39") (pin "1") (pinfunction "1_1") (pintype "passive"))
      (node (ref "D3") (pin "20") (pinfunction "AREF_20") (pintype "passive"))
    )
    (net (code "91") (name "Net-(D3-PB6(XTAL1{slash}TOSC1))") (class "Default")
      (node (ref "D3") (pin "7") (pinfunction "PB6(XTAL1/TOSC1)_7") (pintype "bidirectional"))
      (node (ref "Q2") (pin "1") (pinfunction "1_1") (pintype "passive"))
    )
    (net (code "92") (name "Net-(D3-PB7(XTAL2{slash}TOSC2))") (class "Default")
      (node (ref "D3") (pin "8") (pinfunction "PB7(XTAL2/TOSC2)_8") (pintype "bidirectional"))
      (node (ref "Q2") (pin "3") (pinfunction "3_3") (pintype "passive"))
    )
    (net (code "93") (name "Net-(D4-AREF)") (class "Default")
      (node (ref "C41") (pin "1") (pinfunction "1_1") (pintype "passive"))
      (node (ref "D4") (pin "20") (pinfunction "AREF_20") (pintype "passive"))
    )
    (net (code "94") (name "Net-(D4-PB6(XTAL1{slash}TOSC1))") (class "Default")
      (node (ref "D4") (pin "7") (pinfunction "PB6(XTAL1/TOSC1)_7") (pintype "bidirectional"))
      (node (ref "Q4") (pin "1") (pinfunction "1_1") (pintype "passive"))
    )
    (net (code "95") (name "Net-(D4-PB7(XTAL2{slash}TOSC2))") (class "Default")
      (node (ref "D4") (pin "8") (pinfunction "PB7(XTAL2/TOSC2)_8") (pintype "bidirectional"))
      (node (ref "Q4") (pin "3") (pinfunction "3_3") (pintype "passive"))
    )
    (net (code "96") (name "Net-(H1-PadA)") (class "Default")
      (node (ref "H1") (pin "A") (pinfunction "A_A") (pintype "passive"))
      (node (ref "R47") (pin "1") (pinfunction "1_1") (pintype "passive"))
    )
    (net (code "97") (name "Net-(L1-1)") (class "Default")
      (node (ref "C28") (pin "2") (pinfunction "2_2") (pintype "passive"))
      (node (ref "L1") (pin "P$1") (pinfunction "1_P$1") (pintype "passive"))
      (node (ref "U1") (pin "6") (pinfunction "SW_6") (pintype "bidirectional"))
      (node (ref "V26") (pin "C") (pinfunction "C_C") (pintype "passive"))
    )
    (net (code "98") (name "Net-(N1-BOOT)") (class "Default")
      (node (ref "C4") (pin "1") (pinfunction "1_1") (pintype "passive"))
      (node (ref "N1") (pin "7") (pinfunction "BOOT_7") (pintype "bidirectional"))
    )
    (net (code "99") (name "Net-(N1-HIGHDR)") (class "Default")
      (node (ref "N1") (pin "8") (pinfunction "HIGHDR_8") (pintype "output"))
      (node (ref "V1") (pin "P$4") (pinfunction "G_P$4") (pintype "passive"))
    )
    (net (code "100") (name "Net-(N1-LOWDR)") (class "Default")
      (node (ref "N1") (pin "5") (pinfunction "LOWDR_5") (pintype "output"))
      (node (ref "V2") (pin "P$4") (pinfunction "G_P$4") (pintype "passive"))
    )
    (net (code "101") (name "Net-(N2-BOOT)") (class "Default")
      (node (ref "C5") (pin "1") (pinfunction "1_1") (pintype "passive"))
      (node (ref "N2") (pin "7") (pinfunction "BOOT_7") (pintype "bidirectional"))
    )
    (net (code "102") (name "Net-(N2-HIGHDR)") (class "Default")
      (node (ref "N2") (pin "8") (pinfunction "HIGHDR_8") (pintype "output"))
      (node (ref "V3") (pin "P$4") (pinfunction "G_P$4") (pintype "passive"))
    )
    (net (code "103") (name "Net-(N2-LOWDR)") (class "Default")
      (node (ref "N2") (pin "5") (pinfunction "LOWDR_5") (pintype "output"))
      (node (ref "V4") (pin "P$4") (pinfunction "G_P$4") (pintype "passive"))
    )
    (net (code "104") (name "Net-(N3-BOOT)") (class "Default")
      (node (ref "C6") (pin "1") (pinfunction "1_1") (pintype "passive"))
      (node (ref "N3") (pin "7") (pinfunction "BOOT_7") (pintype "bidirectional"))
    )
    (net (code "105") (name "Net-(N3-HIGHDR)") (class "Default")
      (node (ref "N3") (pin "8") (pinfunction "HIGHDR_8") (pintype "output"))
      (node (ref "V5") (pin "P$4") (pinfunction "G_P$4") (pintype "passive"))
    )
    (net (code "106") (name "Net-(N3-LOWDR)") (class "Default")
      (node (ref "N3") (pin "5") (pinfunction "LOWDR_5") (pintype "output"))
      (node (ref "V6") (pin "P$4") (pinfunction "G_P$4") (pintype "passive"))
    )
    (net (code "107") (name "Net-(N4-BOOT)") (class "Default")
      (node (ref "C7") (pin "1") (pinfunction "1_1") (pintype "passive"))
      (node (ref "N4") (pin "7") (pinfunction "BOOT_7") (pintype "bidirectional"))
    )
    (net (code "108") (name "Net-(N4-HIGHDR)") (class "Default")
      (node (ref "N4") (pin "8") (pinfunction "HIGHDR_8") (pintype "output"))
      (node (ref "V7") (pin "P$4") (pinfunction "G_P$4") (pintype "passive"))
    )
    (net (code "109") (name "Net-(N4-LOWDR)") (class "Default")
      (node (ref "N4") (pin "5") (pinfunction "LOWDR_5") (pintype "output"))
      (node (ref "V8") (pin "P$4") (pinfunction "G_P$4") (pintype "passive"))
    )
    (net (code "110") (name "Net-(N5-BOOT)") (class "Default")
      (node (ref "C10") (pin "1") (pinfunction "1_1") (pintype "passive"))
      (node (ref "N5") (pin "7") (pinfunction "BOOT_7") (pintype "bidirectional"))
    )
    (net (code "111") (name "Net-(N5-HIGHDR)") (class "Default")
      (node (ref "N5") (pin "8") (pinfunction "HIGHDR_8") (pintype "output"))
      (node (ref "V9") (pin "P$4") (pinfunction "G_P$4") (pintype "passive"))
    )
    (net (code "112") (name "Net-(N5-LOWDR)") (class "Default")
      (node (ref "N5") (pin "5") (pinfunction "LOWDR_5") (pintype "output"))
      (node (ref "V10") (pin "P$4") (pinfunction "G_P$4") (pintype "passive"))
    )
    (net (code "113") (name "Net-(N6-BOOT)") (class "Default")
      (node (ref "C11") (pin "1") (pinfunction "1_1") (pintype "passive"))
      (node (ref "N6") (pin "7") (pinfunction "BOOT_7") (pintype "bidirectional"))
    )
    (net (code "114") (name "Net-(N6-HIGHDR)") (class "Default")
      (node (ref "N6") (pin "8") (pinfunction "HIGHDR_8") (pintype "output"))
      (node (ref "V11") (pin "P$4") (pinfunction "G_P$4") (pintype "passive"))
    )
    (net (code "115") (name "Net-(N6-LOWDR)") (class "Default")
      (node (ref "N6") (pin "5") (pinfunction "LOWDR_5") (pintype "output"))
      (node (ref "V12") (pin "P$4") (pinfunction "G_P$4") (pintype "passive"))
    )
    (net (code "116") (name "Net-(N7-BOOT)") (class "Default")
      (node (ref "C13") (pin "1") (pinfunction "1_1") (pintype "passive"))
      (node (ref "N7") (pin "7") (pinfunction "BOOT_7") (pintype "bidirectional"))
    )
    (net (code "117") (name "Net-(N7-HIGHDR)") (class "Default")
      (node (ref "N7") (pin "8") (pinfunction "HIGHDR_8") (pintype "output"))
      (node (ref "V13") (pin "P$4") (pinfunction "G_P$4") (pintype "passive"))
    )
    (net (code "118") (name "Net-(N7-LOWDR)") (class "Default")
      (node (ref "N7") (pin "5") (pinfunction "LOWDR_5") (pintype "output"))
      (node (ref "V14") (pin "P$4") (pinfunction "G_P$4") (pintype "passive"))
    )
    (net (code "119") (name "Net-(N8-BOOT)") (class "Default")
      (node (ref "C16") (pin "1") (pinfunction "1_1") (pintype "passive"))
      (node (ref "N8") (pin "7") (pinfunction "BOOT_7") (pintype "bidirectional"))
    )
    (net (code "120") (name "Net-(N8-HIGHDR)") (class "Default")
      (node (ref "N8") (pin "8") (pinfunction "HIGHDR_8") (pintype "output"))
      (node (ref "V15") (pin "P$4") (pinfunction "G_P$4") (pintype "passive"))
    )
    (net (code "121") (name "Net-(N8-LOWDR)") (class "Default")
      (node (ref "N8") (pin "5") (pinfunction "LOWDR_5") (pintype "output"))
      (node (ref "V16") (pin "P$4") (pinfunction "G_P$4") (pintype "passive"))
    )
    (net (code "122") (name "Net-(N9-BOOT)") (class "Default")
      (node (ref "C17") (pin "1") (pinfunction "1_1") (pintype "passive"))
      (node (ref "N9") (pin "7") (pinfunction "BOOT_7") (pintype "bidirectional"))
    )
    (net (code "123") (name "Net-(N9-HIGHDR)") (class "Default")
      (node (ref "N9") (pin "8") (pinfunction "HIGHDR_8") (pintype "output"))
      (node (ref "V17") (pin "P$4") (pinfunction "G_P$4") (pintype "passive"))
    )
    (net (code "124") (name "Net-(N9-LOWDR)") (class "Default")
      (node (ref "N9") (pin "5") (pinfunction "LOWDR_5") (pintype "output"))
      (node (ref "V18") (pin "P$4") (pinfunction "G_P$4") (pintype "passive"))
    )
    (net (code "125") (name "Net-(N10-BOOT)") (class "Default")
      (node (ref "C19") (pin "1") (pinfunction "1_1") (pintype "passive"))
      (node (ref "N10") (pin "7") (pinfunction "BOOT_7") (pintype "bidirectional"))
    )
    (net (code "126") (name "Net-(N10-HIGHDR)") (class "Default")
      (node (ref "N10") (pin "8") (pinfunction "HIGHDR_8") (pintype "output"))
      (node (ref "V19") (pin "P$4") (pinfunction "G_P$4") (pintype "passive"))
    )
    (net (code "127") (name "Net-(N10-LOWDR)") (class "Default")
      (node (ref "N10") (pin "5") (pinfunction "LOWDR_5") (pintype "output"))
      (node (ref "V20") (pin "P$4") (pinfunction "G_P$4") (pintype "passive"))
    )
    (net (code "128") (name "Net-(N11-BOOT)") (class "Default")
      (node (ref "C22") (pin "1") (pinfunction "1_1") (pintype "passive"))
      (node (ref "N11") (pin "7") (pinfunction "BOOT_7") (pintype "bidirectional"))
    )
    (net (code "129") (name "Net-(N11-HIGHDR)") (class "Default")
      (node (ref "N11") (pin "8") (pinfunction "HIGHDR_8") (pintype "output"))
      (node (ref "V21") (pin "P$4") (pinfunction "G_P$4") (pintype "passive"))
    )
    (net (code "130") (name "Net-(N11-LOWDR)") (class "Default")
      (node (ref "N11") (pin "5") (pinfunction "LOWDR_5") (pintype "output"))
      (node (ref "V22") (pin "P$4") (pinfunction "G_P$4") (pintype "passive"))
    )
    (net (code "131") (name "Net-(N12-BOOT)") (class "Default")
      (node (ref "C23") (pin "1") (pinfunction "1_1") (pintype "passive"))
      (node (ref "N12") (pin "7") (pinfunction "BOOT_7") (pintype "bidirectional"))
    )
    (net (code "132") (name "Net-(N12-HIGHDR)") (class "Default")
      (node (ref "N12") (pin "8") (pinfunction "HIGHDR_8") (pintype "output"))
      (node (ref "V23") (pin "P$4") (pinfunction "G_P$4") (pintype "passive"))
    )
    (net (code "133") (name "Net-(N12-LOWDR)") (class "Default")
      (node (ref "N12") (pin "5") (pinfunction "LOWDR_5") (pintype "output"))
      (node (ref "V24") (pin "P$4") (pinfunction "G_P$4") (pintype "passive"))
    )
    (net (code "134") (name "Net-(RN1C-2)") (class "Default")
      (node (ref "H3") (pin "A") (pinfunction "A_A") (pintype "passive"))
      (node (ref "RN1") (pin "6") (pinfunction "2_6") (pintype "passive"))
    )
    (net (code "135") (name "Net-(RN1D-2)") (class "Default")
      (node (ref "H2") (pin "A") (pinfunction "A_A") (pintype "passive"))
      (node (ref "RN1") (pin "5") (pinfunction "2_5") (pintype "passive"))
    )
    (net (code "136") (name "Net-(RN6C-2)") (class "Default")
      (node (ref "H5") (pin "A") (pinfunction "A_A") (pintype "passive"))
      (node (ref "RN6") (pin "6") (pinfunction "2_6") (pintype "passive"))
    )
    (net (code "137") (name "Net-(RN6D-2)") (class "Default")
      (node (ref "H4") (pin "A") (pinfunction "A_A") (pintype "passive"))
      (node (ref "RN6") (pin "5") (pinfunction "2_5") (pintype "passive"))
    )
    (net (code "138") (name "Net-(RN10C-2)") (class "Default")
      (node (ref "H7") (pin "A") (pinfunction "A_A") (pintype "passive"))
      (node (ref "RN10") (pin "6") (pinfunction "2_6") (pintype "passive"))
    )
    (net (code "139") (name "Net-(RN10D-2)") (class "Default")
      (node (ref "H6") (pin "A") (pinfunction "A_A") (pintype "passive"))
      (node (ref "RN10") (pin "5") (pinfunction "2_5") (pintype "passive"))
    )
    (net (code "140") (name "Net-(RN14C-2)") (class "Default")
      (node (ref "H9") (pin "A") (pinfunction "A_A") (pintype "passive"))
      (node (ref "RN14") (pin "6") (pinfunction "2_6") (pintype "passive"))
    )
    (net (code "141") (name "Net-(RN14D-2)") (class "Default")
      (node (ref "H8") (pin "A") (pinfunction "A_A") (pintype "passive"))
      (node (ref "RN14") (pin "5") (pinfunction "2_5") (pintype "passive"))
    )
    (net (code "142") (name "Net-(U1-CB)") (class "Default")
      (node (ref "C28") (pin "1") (pinfunction "1_1") (pintype "passive"))
      (node (ref "U1") (pin "1") (pinfunction "CB_1") (pintype "bidirectional"))
    )
    (net (code "143") (name "Net-(U1-FB)") (class "Default")
      (node (ref "R45") (pin "1") (pinfunction "1_1") (pintype "passive"))
      (node (ref "R46") (pin "2") (pinfunction "2_2") (pintype "passive"))
      (node (ref "U1") (pin "3") (pinfunction "FB_3") (pintype "bidirectional"))
    )
    (net (code "144") (name "PWM_IN_1") (class "Default")
      (node (ref "C3") (pin "1") (pinfunction "1_1") (pintype "passive"))
      (node (ref "R2") (pin "1") (pinfunction "1_1") (pintype "passive"))
      (node (ref "X1") (pin "4") (pinfunction "S_4") (pintype "passive"))
    )
    (net (code "145") (name "PWM_IN_2") (class "Default")
      (node (ref "C8") (pin "1") (pinfunction "1_1") (pintype "passive"))
      (node (ref "R12") (pin "1") (pinfunction "1_1") (pintype "passive"))
      (node (ref "X1") (pin "3") (pinfunction "S_3") (pintype "passive"))
    )
    (net (code "146") (name "PWM_IN_3") (class "Default")
      (node (ref "C14") (pin "1") (pinfunction "1_1") (pintype "passive"))
      (node (ref "R23") (pin "1") (pinfunction "1_1") (pintype "passive"))
      (node (ref "X1") (pin "2") (pinfunction "S_2") (pintype "passive"))
    )
    (net (code "147") (name "PWM_IN_4") (class "Default")
      (node (ref "C20") (pin "1") (pinfunction "1_1") (pintype "passive"))
      (node (ref "R34") (pin "1") (pinfunction "1_1") (pintype "passive"))
      (node (ref "X1") (pin "1") (pinfunction "S_1") (pintype "passive"))
    )
    (net (code "148") (name "RC_IN_1") (class "Default")
      (node (ref "D1") (pin "32") (pinfunction "PD2(INT0)_32") (pintype "bidirectional"))
      (node (ref "R2") (pin "2") (pinfunction "2_2") (pintype "passive"))
    )
    (net (code "149") (name "RC_IN_2") (class "Default")
      (node (ref "D3") (pin "32") (pinfunction "PD2(INT0)_32") (pintype "bidirectional"))
      (node (ref "R12") (pin "2") (pinfunction "2_2") (pintype "passive"))
    )
    (net (code "150") (name "RC_IN_3") (class "Default")
      (node (ref "D2") (pin "32") (pinfunction "PD2(INT0)_32") (pintype "bidirectional"))
      (node (ref "R23") (pin "2") (pinfunction "2_2") (pintype "passive"))
    )
    (net (code "151") (name "RC_IN_4") (class "Default")
      (node (ref "D4") (pin "32") (pinfunction "PD2(INT0)_32") (pintype "bidirectional"))
      (node (ref "R34") (pin "2") (pinfunction "2_2") (pintype "passive"))
    )
    (net (code "152") (name "RED_LED_1") (class "Default")
      (node (ref "D1") (pin "1") (pinfunction "PD3(INT1)_1") (pintype "bidirectional"))
      (node (ref "RN1") (pin "3") (pinfunction "1_3") (pintype "passive"))
    )
    (net (code "153") (name "RED_LED_2") (class "Default")
      (node (ref "D3") (pin "1") (pinfunction "PD3(INT1)_1") (pintype "bidirectional"))
      (node (ref "RN6") (pin "3") (pinfunction "1_3") (pintype "passive"))
    )
    (net (code "154") (name "RED_LED_3") (class "Default")
      (node (ref "D2") (pin "1") (pinfunction "PD3(INT1)_1") (pintype "bidirectional"))
      (node (ref "RN10") (pin "3") (pinfunction "1_3") (pintype "passive"))
    )
    (net (code "155") (name "RED_LED_4") (class "Default")
      (node (ref "D4") (pin "1") (pinfunction "PD3(INT1)_1") (pintype "bidirectional"))
      (node (ref "RN14") (pin "3") (pinfunction "1_3") (pintype "passive"))
    )
    (net (code "156") (name "RST_1") (class "Default")
      (node (ref "C2") (pin "1") (pinfunction "1_1") (pintype "passive"))
      (node (ref "D1") (pin "29") (pinfunction "PC6(/RESET)_29") (pintype "bidirectional"))
      (node (ref "R1") (pin "1") (pinfunction "1_1") (pintype "passive"))
    )
    (net (code "157") (name "RST_2") (class "Default")
      (node (ref "C12") (pin "1") (pinfunction "1_1") (pintype "passive"))
      (node (ref "D3") (pin "29") (pinfunction "PC6(/RESET)_29") (pintype "bidirectional"))
      (node (ref "R13") (pin "1") (pinfunction "1_1") (pintype "passive"))
    )
    (net (code "158") (name "RST_3") (class "Default")
      (node (ref "C18") (pin "1") (pinfunction "1_1") (pintype "passive"))
      (node (ref "D2") (pin "29") (pinfunction "PC6(/RESET)_29") (pintype "bidirectional"))
      (node (ref "R24") (pin "1") (pinfunction "1_1") (pintype "passive"))
    )
    (net (code "159") (name "RST_4") (class "Default")
      (node (ref "C24") (pin "1") (pinfunction "1_1") (pintype "passive"))
      (node (ref "D4") (pin "29") (pinfunction "PC6(/RESET)_29") (pintype "bidirectional"))
      (node (ref "R35") (pin "1") (pinfunction "1_1") (pintype "passive"))
    )
    (net (code "160") (name "SCL") (class "Default")
      (node (ref "D1") (pin "28") (pinfunction "PC5(ADC5/SCL)_28") (pintype "bidirectional"))
      (node (ref "D2") (pin "28") (pinfunction "PC5(ADC5/SCL)_28") (pintype "bidirectional"))
      (node (ref "D3") (pin "28") (pinfunction "PC5(ADC5/SCL)_28") (pintype "bidirectional"))
      (node (ref "D4") (pin "28") (pinfunction "PC5(ADC5/SCL)_28") (pintype "bidirectional"))
      (node (ref "RN17") (pin "2") (pinfunction "1_2") (pintype "passive"))
      (node (ref "X2") (pin "2") (pinfunction "S_2") (pintype "passive"))
    )
    (net (code "161") (name "SDA") (class "Default")
      (node (ref "D1") (pin "27") (pinfunction "PC4(ADC4/SDA)_27") (pintype "bidirectional"))
      (node (ref "D2") (pin "27") (pinfunction "PC4(ADC4/SDA)_27") (pintype "bidirectional"))
      (node (ref "D3") (pin "27") (pinfunction "PC4(ADC4/SDA)_27") (pintype "bidirectional"))
      (node (ref "D4") (pin "27") (pinfunction "PC4(ADC4/SDA)_27") (pintype "bidirectional"))
      (node (ref "RN17") (pin "1") (pinfunction "1_1") (pintype "passive"))
      (node (ref "X2") (pin "3") (pinfunction "S_3") (pintype "passive"))
    )
    (net (code "162") (name "SENSE_STAR_1") (class "Default")
      (node (ref "D1") (pin "10") (pinfunction "PD6(AIN0)_10") (pintype "bidirectional"))
      (node (ref "RN2") (pin "1") (pinfunction "1_1") (pintype "passive"))
      (node (ref "RN2") (pin "2") (pinfunction "1_2") (pintype "passive"))
      (node (ref "RN2") (pin "3") (pinfunction "1_3") (pintype "passive"))
      (node (ref "RN2") (pin "4") (pinfunction "1_4") (pintype "passive"))
    )
    (net (code "163") (name "SENSE_STAR_2") (class "Default")
      (node (ref "D3") (pin "10") (pinfunction "PD6(AIN0)_10") (pintype "bidirectional"))
      (node (ref "RN8") (pin "1") (pinfunction "1_1") (pintype "passive"))
      (node (ref "RN8") (pin "2") (pinfunction "1_2") (pintype "passive"))
      (node (ref "RN8") (pin "3") (pinfunction "1_3") (pintype "passive"))
      (node (ref "RN8") (pin "4") (pinfunction "1_4") (pintype "passive"))
    )
    (net (code "164") (name "SENSE_STAR_3") (class "Default")
      (node (ref "D2") (pin "10") (pinfunction "PD6(AIN0)_10") (pintype "bidirectional"))
      (node (ref "RN12") (pin "1") (pinfunction "1_1") (pintype "passive"))
      (node (ref "RN12") (pin "2") (pinfunction "1_2") (pintype "passive"))
      (node (ref "RN12") (pin "3") (pinfunction "1_3") (pintype "passive"))
      (node (ref "RN12") (pin "4") (pinfunction "1_4") (pintype "passive"))
    )
    (net (code "165") (name "SENSE_STAR_4") (class "Default")
      (node (ref "D4") (pin "10") (pinfunction "PD6(AIN0)_10") (pintype "bidirectional"))
      (node (ref "RN16") (pin "1") (pinfunction "1_1") (pintype "passive"))
      (node (ref "RN16") (pin "2") (pinfunction "1_2") (pintype "passive"))
      (node (ref "RN16") (pin "3") (pinfunction "1_3") (pintype "passive"))
      (node (ref "RN16") (pin "4") (pinfunction "1_4") (pintype "passive"))
    )
    (net (code "166") (name "VCC") (class "Default")
      (node (ref "C25") (pin "1") (pinfunction "1_1") (pintype "passive"))
      (node (ref "C26") (pin "1") (pinfunction "1_1") (pintype "passive"))
      (node (ref "C31") (pin "1") (pinfunction "1_1") (pintype "passive"))
      (node (ref "C32") (pin "1") (pinfunction "1_1") (pintype "passive"))
      (node (ref "C33") (pin "1") (pinfunction "1_1") (pintype "passive"))
      (node (ref "C34") (pin "1") (pinfunction "1_1") (pintype "passive"))
      (node (ref "C35") (pin "1") (pinfunction "1_1") (pintype "passive"))
      (node (ref "C36") (pin "1") (pinfunction "1_1") (pintype "passive"))
      (node (ref "C38") (pin "2") (pinfunction "2_2") (pintype "passive"))
      (node (ref "C50") (pin "+") (pinfunction "+_+") (pintype "passive"))
      (node (ref "C50") (pin "+1") (pinfunction "+_+1") (pintype "passive"))
      (node (ref "C51") (pin "+") (pinfunction "+_+") (pintype "passive"))
      (node (ref "C51") (pin "+1") (pinfunction "+_+1") (pintype "passive"))
      (node (ref "C52") (pin "+") (pinfunction "+_+") (pintype "passive"))
      (node (ref "C52") (pin "+1") (pinfunction "+_+1") (pintype "passive"))
      (node (ref "C53") (pin "+") (pinfunction "+_+") (pintype "passive"))
      (node (ref "C53") (pin "+1") (pinfunction "+_+1") (pintype "passive"))
      (node (ref "C54") (pin "+") (pinfunction "+_+") (pintype "passive"))
      (node (ref "C54") (pin "+1") (pinfunction "+_+1") (pintype "passive"))
      (node (ref "C55") (pin "+") (pinfunction "+_+") (pintype "passive"))
      (node (ref "C55") (pin "+1") (pinfunction "+_+1") (pintype "passive"))
      (node (ref "C56") (pin "+") (pinfunction "+_+") (pintype "passive"))
      (node (ref "C56") (pin "+1") (pinfunction "+_+1") (pintype "passive"))
      (node (ref "JP1") (pin "2") (pinfunction "2_2") (pintype "passive"))
      (node (ref "JP2") (pin "2") (pinfunction "2_2") (pintype "passive"))
      (node (ref "U1") (pin "4") (pinfunction "SHDN_4") (pintype "bidirectional"))
      (node (ref "U1") (pin "5") (pinfunction "VIN_5") (pintype "bidirectional"))
      (node (ref "V1") (pin "P$5") (pinfunction "D_P$5") (pintype "passive"))
      (node (ref "V1") (pin "P$6") (pinfunction "D_P$6") (pintype "passive"))
      (node (ref "V1") (pin "P$7") (pinfunction "D_P$7") (pintype "passive"))
      (node (ref "V1") (pin "P$8") (pinfunction "D_P$8") (pintype "passive"))
      (node (ref "V1") (pin "P$9") (pinfunction "D_P$9") (pintype "passive"))
      (node (ref "V11") (pin "P$5") (pinfunction "D_P$5") (pintype "passive"))
      (node (ref "V11") (pin "P$6") (pinfunction "D_P$6") (pintype "passive"))
      (node (ref "V11") (pin "P$7") (pinfunction "D_P$7") (pintype "passive"))
      (node (ref "V11") (pin "P$8") (pinfunction "D_P$8") (pintype "passive"))
      (node (ref "V11") (pin "P$9") (pinfunction "D_P$9") (pintype "passive"))
      (node (ref "V13") (pin "P$5") (pinfunction "D_P$5") (pintype "passive"))
      (node (ref "V13") (pin "P$6") (pinfunction "D_P$6") (pintype "passive"))
      (node (ref "V13") (pin "P$7") (pinfunction "D_P$7") (pintype "passive"))
      (node (ref "V13") (pin "P$8") (pinfunction "D_P$8") (pintype "passive"))
      (node (ref "V13") (pin "P$9") (pinfunction "D_P$9") (pintype "passive"))
      (node (ref "V15") (pin "P$5") (pinfunction "D_P$5") (pintype "passive"))
      (node (ref "V15") (pin "P$6") (pinfunction "D_P$6") (pintype "passive"))
      (node (ref "V15") (pin "P$7") (pinfunction "D_P$7") (pintype "passive"))
      (node (ref "V15") (pin "P$8") (pinfunction "D_P$8") (pintype "passive"))
      (node (ref "V15") (pin "P$9") (pinfunction "D_P$9") (pintype "passive"))
      (node (ref "V17") (pin "P$5") (pinfunction "D_P$5") (pintype "passive"))
      (node (ref "V17") (pin "P$6") (pinfunction "D_P$6") (pintype "passive"))
      (node (ref "V17") (pin "P$7") (pinfunction "D_P$7") (pintype "passive"))
      (node (ref "V17") (pin "P$8") (pinfunction "D_P$8") (pintype "passive"))
      (node (ref "V17") (pin "P$9") (pinfunction "D_P$9") (pintype "passive"))
      (node (ref "V19") (pin "P$5") (pinfunction "D_P$5") (pintype "passive"))
      (node (ref "V19") (pin "P$6") (pinfunction "D_P$6") (pintype "passive"))
      (node (ref "V19") (pin "P$7") (pinfunction "D_P$7") (pintype "passive"))
      (node (ref "V19") (pin "P$8") (pinfunction "D_P$8") (pintype "passive"))
      (node (ref "V19") (pin "P$9") (pinfunction "D_P$9") (pintype "passive"))
      (node (ref "V21") (pin "P$5") (pinfunction "D_P$5") (pintype "passive"))
      (node (ref "V21") (pin "P$6") (pinfunction "D_P$6") (pintype "passive"))
      (node (ref "V21") (pin "P$7") (pinfunction "D_P$7") (pintype "passive"))
      (node (ref "V21") (pin "P$8") (pinfunction "D_P$8") (pintype "passive"))
      (node (ref "V21") (pin "P$9") (pinfunction "D_P$9") (pintype "passive"))
      (node (ref "V23") (pin "P$5") (pinfunction "D_P$5") (pintype "passive"))
      (node (ref "V23") (pin "P$6") (pinfunction "D_P$6") (pintype "passive"))
      (node (ref "V23") (pin "P$7") (pinfunction "D_P$7") (pintype "passive"))
      (node (ref "V23") (pin "P$8") (pinfunction "D_P$8") (pintype "passive"))
      (node (ref "V23") (pin "P$9") (pinfunction "D_P$9") (pintype "passive"))
      (node (ref "V3") (pin "P$5") (pinfunction "D_P$5") (pintype "passive"))
      (node (ref "V3") (pin "P$6") (pinfunction "D_P$6") (pintype "passive"))
      (node (ref "V3") (pin "P$7") (pinfunction "D_P$7") (pintype "passive"))
      (node (ref "V3") (pin "P$8") (pinfunction "D_P$8") (pintype "passive"))
      (node (ref "V3") (pin "P$9") (pinfunction "D_P$9") (pintype "passive"))
      (node (ref "V5") (pin "P$5") (pinfunction "D_P$5") (pintype "passive"))
      (node (ref "V5") (pin "P$6") (pinfunction "D_P$6") (pintype "passive"))
      (node (ref "V5") (pin "P$7") (pinfunction "D_P$7") (pintype "passive"))
      (node (ref "V5") (pin "P$8") (pinfunction "D_P$8") (pintype "passive"))
      (node (ref "V5") (pin "P$9") (pinfunction "D_P$9") (pintype "passive"))
      (node (ref "V7") (pin "P$5") (pinfunction "D_P$5") (pintype "passive"))
      (node (ref "V7") (pin "P$6") (pinfunction "D_P$6") (pintype "passive"))
      (node (ref "V7") (pin "P$7") (pinfunction "D_P$7") (pintype "passive"))
      (node (ref "V7") (pin "P$8") (pinfunction "D_P$8") (pintype "passive"))
      (node (ref "V7") (pin "P$9") (pinfunction "D_P$9") (pintype "passive"))
      (node (ref "V9") (pin "P$5") (pinfunction "D_P$5") (pintype "passive"))
      (node (ref "V9") (pin "P$6") (pinfunction "D_P$6") (pintype "passive"))
      (node (ref "V9") (pin "P$7") (pinfunction "D_P$7") (pintype "passive"))
      (node (ref "V9") (pin "P$8") (pinfunction "D_P$8") (pintype "passive"))
      (node (ref "V9") (pin "P$9") (pinfunction "D_P$9") (pintype "passive"))
    )
    (net (code "167") (name "unconnected-(RN2C-2-Pad6)") (class "Default")
      (node (ref "RN2") (pin "6") (pinfunction "2_6") (pintype "passive"))
    )
    (net (code "168") (name "unconnected-(RN3C-2-Pad6)") (class "Default")
      (node (ref "RN3") (pin "6") (pinfunction "2_6") (pintype "passive"))
    )
    (net (code "169") (name "unconnected-(RN4C-2-Pad6)") (class "Default")
      (node (ref "RN4") (pin "6") (pinfunction "2_6") (pintype "passive"))
    )
    (net (code "170") (name "unconnected-(RN5C-2-Pad6)") (class "Default")
      (node (ref "RN5") (pin "6") (pinfunction "2_6") (pintype "passive"))
    )
    (net (code "171") (name "unconnected-(RN7C-2-Pad6)") (class "Default")
      (node (ref "RN7") (pin "6") (pinfunction "2_6") (pintype "passive"))
    )
    (net (code "172") (name "unconnected-(RN8C-2-Pad6)") (class "Default")
      (node (ref "RN8") (pin "6") (pinfunction "2_6") (pintype "passive"))
    )
    (net (code "173") (name "unconnected-(RN9C-2-Pad6)") (class "Default")
      (node (ref "RN9") (pin "6") (pinfunction "2_6") (pintype "passive"))
    )
    (net (code "174") (name "unconnected-(RN11C-2-Pad6)") (class "Default")
      (node (ref "RN11") (pin "6") (pinfunction "2_6") (pintype "passive"))
    )
    (net (code "175") (name "unconnected-(RN12C-2-Pad6)") (class "Default")
      (node (ref "RN12") (pin "6") (pinfunction "2_6") (pintype "passive"))
    )
    (net (code "176") (name "unconnected-(RN13C-2-Pad6)") (class "Default")
      (node (ref "RN13") (pin "6") (pinfunction "2_6") (pintype "passive"))
    )
    (net (code "177") (name "unconnected-(RN15C-2-Pad6)") (class "Default")
      (node (ref "RN15") (pin "6") (pinfunction "2_6") (pintype "passive"))
    )
    (net (code "178") (name "unconnected-(RN16C-2-Pad6)") (class "Default")
      (node (ref "RN16") (pin "6") (pinfunction "2_6") (pintype "passive"))
    )
  )
)
